# 02-8_Motors.net
KiCad netlist of a schematic drawn in Altium Designer
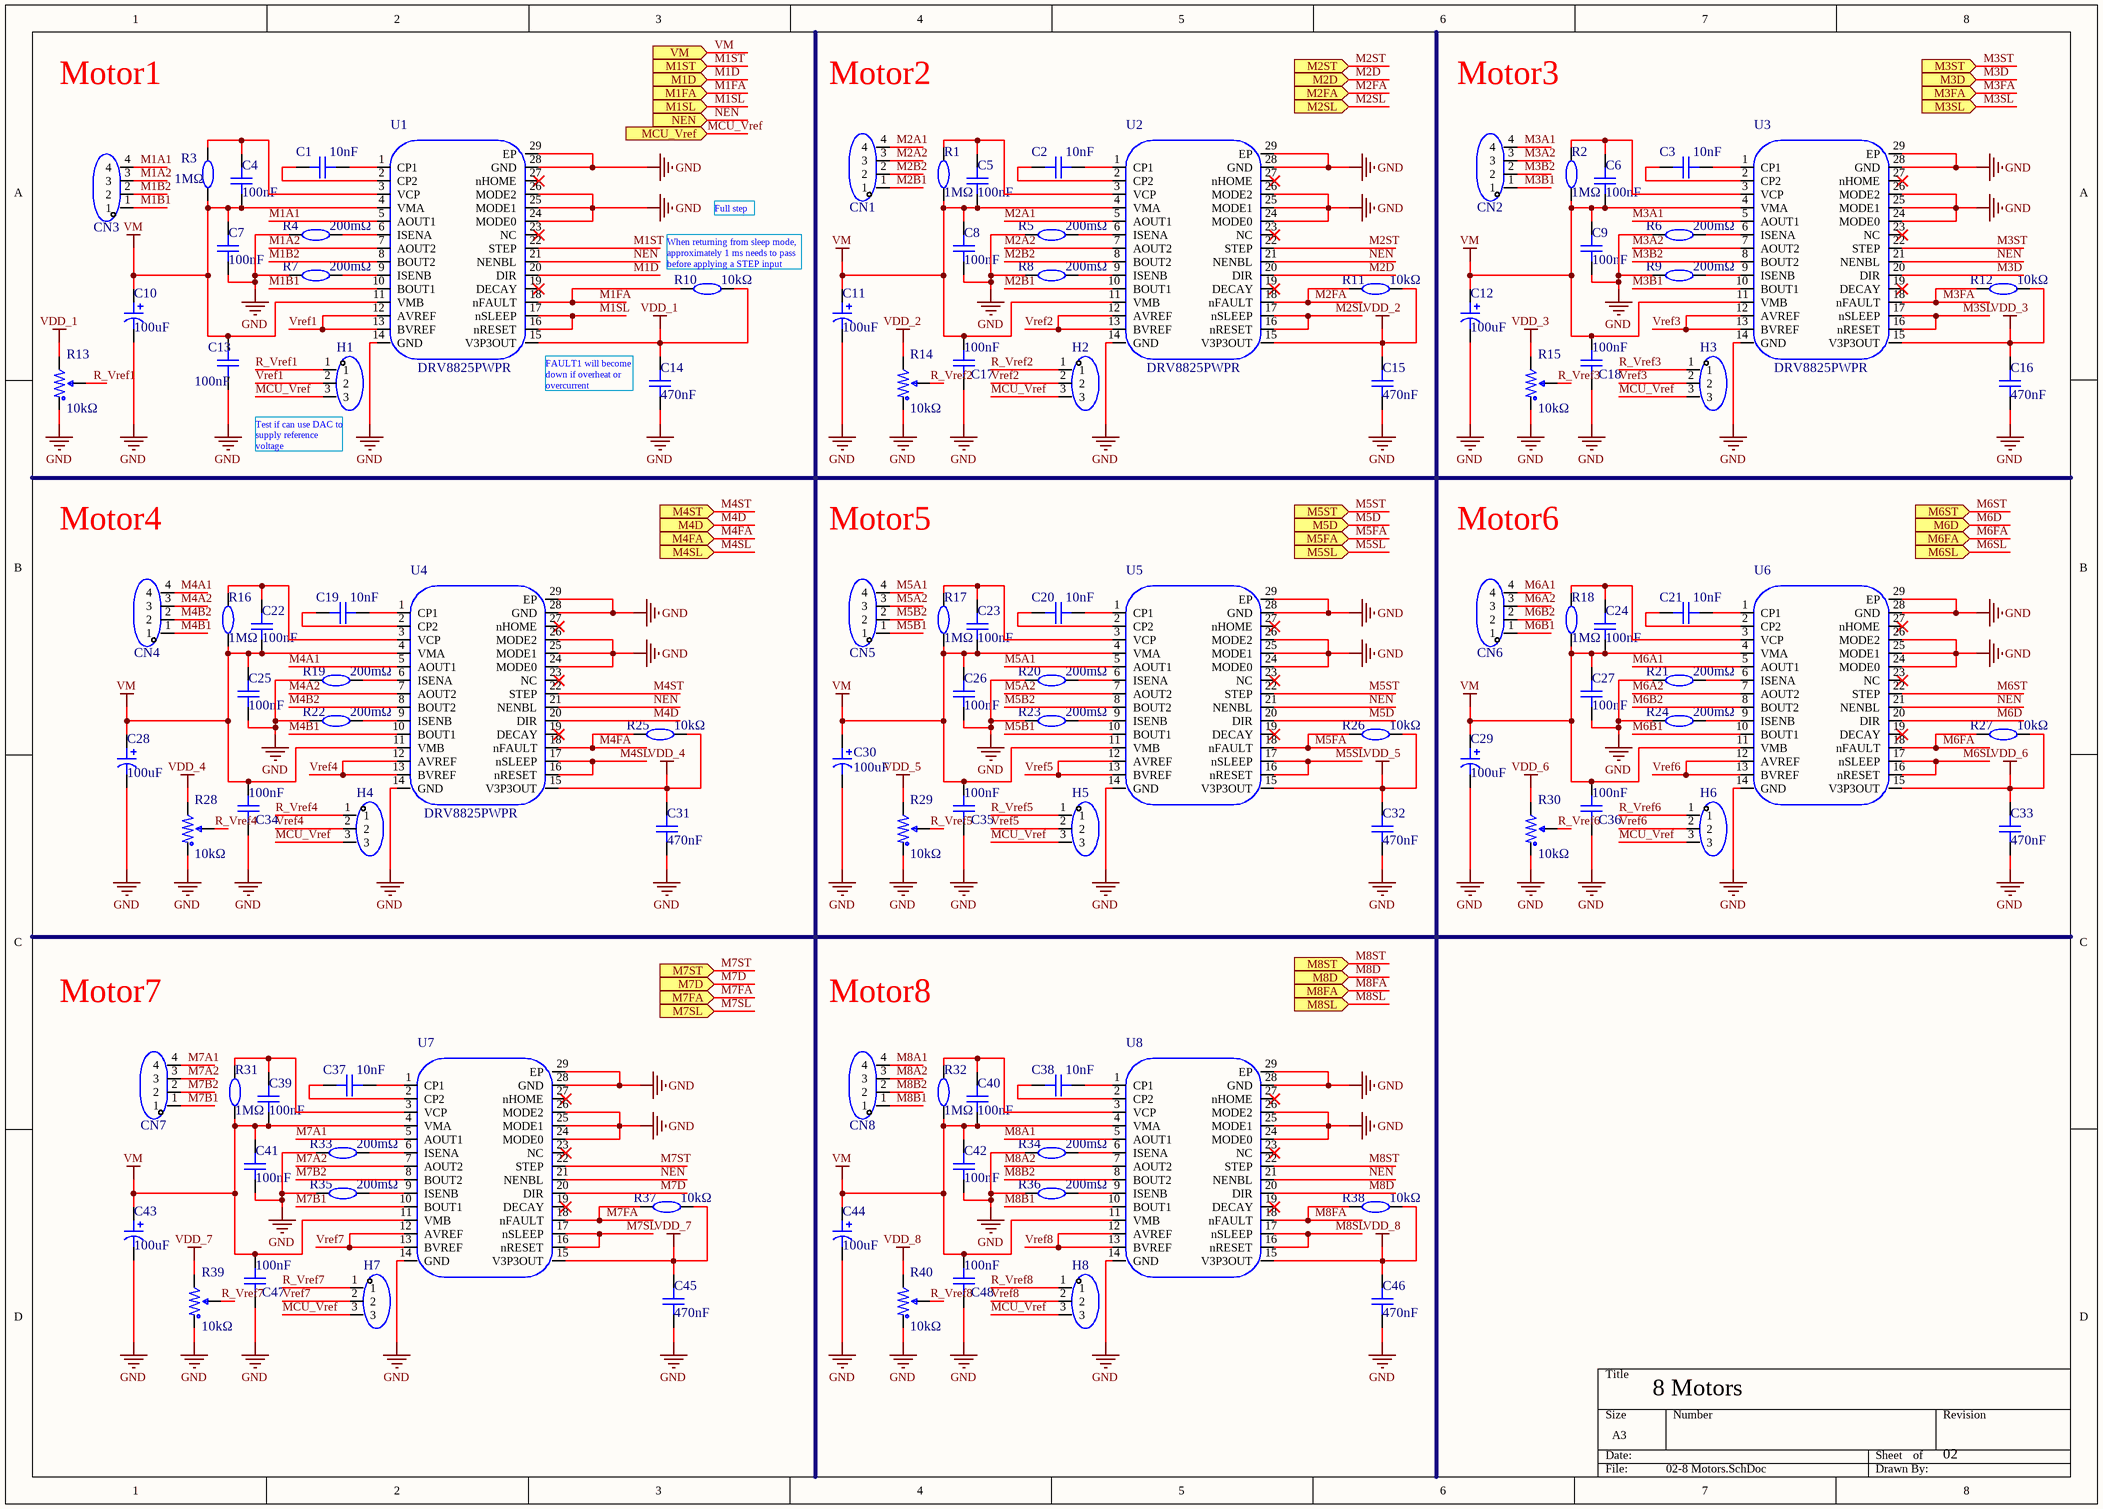
[diagram p0: 02-8 Motors.SchDoc]

(export (version "E")
  (design (tool "Eeschema 10.0.6"))
  (components
    (comp (ref "C1")
      (value "10nF")
      (footprint "C0603")
      (description "0603电容")
      (fields
        (field (name "MANUFACTURER") "SAMSUNG(三星)")
        (field (name "MANUFACTURER PART") "CC0603KRX7R9BB104")
      )
      (libsource (lib "SchLib") (part "C0603_10nF"))
    )
    (comp (ref "C2")
      (value "10nF")
      (footprint "C0603")
      (description "0603电容")
      (fields
        (field (name "MANUFACTURER") "SAMSUNG(三星)")
        (field (name "MANUFACTURER PART") "CC0603KRX7R9BB104")
      )
      (libsource (lib "SchLib") (part "C0603_10nF"))
    )
    (comp (ref "C3")
      (value "10nF")
      (footprint "C0603")
      (description "0603电容")
      (fields
        (field (name "MANUFACTURER") "SAMSUNG(三星)")
        (field (name "MANUFACTURER PART") "CC0603KRX7R9BB104")
      )
      (libsource (lib "SchLib") (part "C0603_10nF"))
    )
    (comp (ref "C4")
      (value "100nF")
      (footprint "C0603")
      (description "0603电容")
      (fields
        (field (name "MANUFACTURER") "SAMSUNG(三星)")
        (field (name "MANUFACTURER PART") "CC0603KRX7R9BB104")
      )
      (libsource (lib "SchLib") (part "C0603_100nF"))
    )
    (comp (ref "C5")
      (value "100nF")
      (footprint "C0603")
      (description "0603电容")
      (fields
        (field (name "MANUFACTURER") "SAMSUNG(三星)")
        (field (name "MANUFACTURER PART") "CC0603KRX7R9BB104")
      )
      (libsource (lib "SchLib") (part "C0603_100nF"))
    )
    (comp (ref "C6")
      (value "100nF")
      (footprint "C0603")
      (description "0603电容")
      (fields
        (field (name "MANUFACTURER") "SAMSUNG(三星)")
        (field (name "MANUFACTURER PART") "CC0603KRX7R9BB104")
      )
      (libsource (lib "SchLib") (part "C0603_100nF"))
    )
    (comp (ref "C7")
      (value "100nF")
      (footprint "C0603")
      (description "0603电容")
      (fields
        (field (name "MANUFACTURER") "SAMSUNG(三星)")
        (field (name "MANUFACTURER PART") "CC0603KRX7R9BB104")
      )
      (libsource (lib "SchLib") (part "C0603_100nF"))
    )
    (comp (ref "C8")
      (value "100nF")
      (footprint "C0603")
      (description "0603电容")
      (fields
        (field (name "MANUFACTURER") "SAMSUNG(三星)")
        (field (name "MANUFACTURER PART") "CC0603KRX7R9BB104")
      )
      (libsource (lib "SchLib") (part "C0603_100nF"))
    )
    (comp (ref "C9")
      (value "100nF")
      (footprint "C0603")
      (description "0603电容")
      (fields
        (field (name "MANUFACTURER") "SAMSUNG(三星)")
        (field (name "MANUFACTURER PART") "CC0603KRX7R9BB104")
      )
      (libsource (lib "SchLib") (part "C0603_100nF"))
    )
    (comp (ref "C10")
      (value "100uF")
      (footprint "SMD6.3_7.7_100uF")
      (description "贴片型铝电解电容 容值 100uF 精度 ±20% 额定电压 35V 纹波电流 87mA@120kHz")
      (fields
        (field (name "MANUFACTURER") "KNSCHA(科尼盛)")
        (field (name "MANUFACTURER PART") "RVT100UF35V67RV0034")
      )
      (libsource (lib "SchLib") (part "SMD6.3_7.7_100uF"))
    )
    (comp (ref "C11")
      (value "100uF")
      (footprint "SMD6.3_7.7_100uF")
      (description "贴片型铝电解电容 容值 100uF 精度 ±20% 额定电压 35V 纹波电流 87mA@120kHz")
      (fields
        (field (name "MANUFACTURER") "KNSCHA(科尼盛)")
        (field (name "MANUFACTURER PART") "RVT100UF35V67RV0034")
      )
      (libsource (lib "SchLib") (part "SMD6.3_7.7_100uF"))
    )
    (comp (ref "C12")
      (value "100uF")
      (footprint "SMD6.3_7.7_100uF")
      (description "贴片型铝电解电容 容值 100uF 精度 ±20% 额定电压 35V 纹波电流 87mA@120kHz")
      (fields
        (field (name "MANUFACTURER") "KNSCHA(科尼盛)")
        (field (name "MANUFACTURER PART") "RVT100UF35V67RV0034")
      )
      (libsource (lib "SchLib") (part "SMD6.3_7.7_100uF"))
    )
    (comp (ref "C13")
      (value "100nF")
      (footprint "C0603")
      (description "0603电容")
      (fields
        (field (name "MANUFACTURER") "SAMSUNG(三星)")
        (field (name "MANUFACTURER PART") "CC0603KRX7R9BB104")
      )
      (libsource (lib "SchLib") (part "C0603_100nF"))
    )
    (comp (ref "C14")
      (value "470nF")
      (footprint "C0603")
      (description "0603电容")
      (fields
        (field (name "MANUFACTURER") "SAMSUNG(三星)")
        (field (name "MANUFACTURER PART") "CC0603KRX7R9BB104")
      )
      (libsource (lib "SchLib") (part "C0603_470nF"))
    )
    (comp (ref "C15")
      (value "470nF")
      (footprint "C0603")
      (description "0603电容")
      (fields
        (field (name "MANUFACTURER") "SAMSUNG(三星)")
        (field (name "MANUFACTURER PART") "CC0603KRX7R9BB104")
      )
      (libsource (lib "SchLib") (part "C0603_470nF"))
    )
    (comp (ref "C16")
      (value "470nF")
      (footprint "C0603")
      (description "0603电容")
      (fields
        (field (name "MANUFACTURER") "SAMSUNG(三星)")
        (field (name "MANUFACTURER PART") "CC0603KRX7R9BB104")
      )
      (libsource (lib "SchLib") (part "C0603_470nF"))
    )
    (comp (ref "C17")
      (value "100nF")
      (footprint "C0603")
      (description "0603电容")
      (fields
        (field (name "MANUFACTURER") "SAMSUNG(三星)")
        (field (name "MANUFACTURER PART") "CC0603KRX7R9BB104")
      )
      (libsource (lib "SchLib") (part "C0603_100nF"))
    )
    (comp (ref "C18")
      (value "100nF")
      (footprint "C0603")
      (description "0603电容")
      (fields
        (field (name "MANUFACTURER") "SAMSUNG(三星)")
        (field (name "MANUFACTURER PART") "CC0603KRX7R9BB104")
      )
      (libsource (lib "SchLib") (part "C0603_100nF"))
    )
    (comp (ref "C19")
      (value "10nF")
      (footprint "C0603")
      (description "0603电容")
      (fields
        (field (name "MANUFACTURER") "SAMSUNG(三星)")
        (field (name "MANUFACTURER PART") "CC0603KRX7R9BB104")
      )
      (libsource (lib "SchLib") (part "C0603_10nF"))
    )
    (comp (ref "C20")
      (value "10nF")
      (footprint "C0603")
      (description "0603电容")
      (fields
        (field (name "MANUFACTURER") "SAMSUNG(三星)")
        (field (name "MANUFACTURER PART") "CC0603KRX7R9BB104")
      )
      (libsource (lib "SchLib") (part "C0603_10nF"))
    )
    (comp (ref "C21")
      (value "10nF")
      (footprint "C0603")
      (description "0603电容")
      (fields
        (field (name "MANUFACTURER") "SAMSUNG(三星)")
        (field (name "MANUFACTURER PART") "CC0603KRX7R9BB104")
      )
      (libsource (lib "SchLib") (part "C0603_10nF"))
    )
    (comp (ref "C22")
      (value "100nF")
      (footprint "C0603")
      (description "0603电容")
      (fields
        (field (name "MANUFACTURER") "SAMSUNG(三星)")
        (field (name "MANUFACTURER PART") "CC0603KRX7R9BB104")
      )
      (libsource (lib "SchLib") (part "C0603_100nF"))
    )
    (comp (ref "C23")
      (value "100nF")
      (footprint "C0603")
      (description "0603电容")
      (fields
        (field (name "MANUFACTURER") "SAMSUNG(三星)")
        (field (name "MANUFACTURER PART") "CC0603KRX7R9BB104")
      )
      (libsource (lib "SchLib") (part "C0603_100nF"))
    )
    (comp (ref "C24")
      (value "100nF")
      (footprint "C0603")
      (description "0603电容")
      (fields
        (field (name "MANUFACTURER") "SAMSUNG(三星)")
        (field (name "MANUFACTURER PART") "CC0603KRX7R9BB104")
      )
      (libsource (lib "SchLib") (part "C0603_100nF"))
    )
    (comp (ref "C25")
      (value "100nF")
      (footprint "C0603")
      (description "0603电容")
      (fields
        (field (name "MANUFACTURER") "SAMSUNG(三星)")
        (field (name "MANUFACTURER PART") "CC0603KRX7R9BB104")
      )
      (libsource (lib "SchLib") (part "C0603_100nF"))
    )
    (comp (ref "C26")
      (value "100nF")
      (footprint "C0603")
      (description "0603电容")
      (fields
        (field (name "MANUFACTURER") "SAMSUNG(三星)")
        (field (name "MANUFACTURER PART") "CC0603KRX7R9BB104")
      )
      (libsource (lib "SchLib") (part "C0603_100nF"))
    )
    (comp (ref "C27")
      (value "100nF")
      (footprint "C0603")
      (description "0603电容")
      (fields
        (field (name "MANUFACTURER") "SAMSUNG(三星)")
        (field (name "MANUFACTURER PART") "CC0603KRX7R9BB104")
      )
      (libsource (lib "SchLib") (part "C0603_100nF"))
    )
    (comp (ref "C28")
      (value "100uF")
      (footprint "SMD6.3_7.7_100uF")
      (description "贴片型铝电解电容 容值 100uF 精度 ±20% 额定电压 35V 纹波电流 87mA@120kHz")
      (fields
        (field (name "MANUFACTURER") "KNSCHA(科尼盛)")
        (field (name "MANUFACTURER PART") "RVT100UF35V67RV0034")
      )
      (libsource (lib "SchLib") (part "SMD6.3_7.7_100uF"))
    )
    (comp (ref "C29")
      (value "100uF")
      (footprint "SMD6.3_7.7_100uF")
      (description "贴片型铝电解电容 容值 100uF 精度 ±20% 额定电压 35V 纹波电流 87mA@120kHz")
      (fields
        (field (name "MANUFACTURER") "KNSCHA(科尼盛)")
        (field (name "MANUFACTURER PART") "RVT100UF35V67RV0034")
      )
      (libsource (lib "SchLib") (part "SMD6.3_7.7_100uF"))
    )
    (comp (ref "C30")
      (value "100uF")
      (footprint "SMD6.3_7.7_100uF")
      (description "贴片型铝电解电容 容值 100uF 精度 ±20% 额定电压 35V 纹波电流 87mA@120kHz")
      (fields
        (field (name "MANUFACTURER") "KNSCHA(科尼盛)")
        (field (name "MANUFACTURER PART") "RVT100UF35V67RV0034")
      )
      (libsource (lib "SchLib") (part "SMD6.3_7.7_100uF"))
    )
    (comp (ref "C31")
      (value "470nF")
      (footprint "C0603")
      (description "0603电容")
      (fields
        (field (name "MANUFACTURER") "SAMSUNG(三星)")
        (field (name "MANUFACTURER PART") "CC0603KRX7R9BB104")
      )
      (libsource (lib "SchLib") (part "C0603_470nF"))
    )
    (comp (ref "C32")
      (value "470nF")
      (footprint "C0603")
      (description "0603电容")
      (fields
        (field (name "MANUFACTURER") "SAMSUNG(三星)")
        (field (name "MANUFACTURER PART") "CC0603KRX7R9BB104")
      )
      (libsource (lib "SchLib") (part "C0603_470nF"))
    )
    (comp (ref "C33")
      (value "470nF")
      (footprint "C0603")
      (description "0603电容")
      (fields
        (field (name "MANUFACTURER") "SAMSUNG(三星)")
        (field (name "MANUFACTURER PART") "CC0603KRX7R9BB104")
      )
      (libsource (lib "SchLib") (part "C0603_470nF"))
    )
    (comp (ref "C34")
      (value "100nF")
      (footprint "C0603")
      (description "0603电容")
      (fields
        (field (name "MANUFACTURER") "SAMSUNG(三星)")
        (field (name "MANUFACTURER PART") "CC0603KRX7R9BB104")
      )
      (libsource (lib "SchLib") (part "C0603_100nF"))
    )
    (comp (ref "C35")
      (value "100nF")
      (footprint "C0603")
      (description "0603电容")
      (fields
        (field (name "MANUFACTURER") "SAMSUNG(三星)")
        (field (name "MANUFACTURER PART") "CC0603KRX7R9BB104")
      )
      (libsource (lib "SchLib") (part "C0603_100nF"))
    )
    (comp (ref "C36")
      (value "100nF")
      (footprint "C0603")
      (description "0603电容")
      (fields
        (field (name "MANUFACTURER") "SAMSUNG(三星)")
        (field (name "MANUFACTURER PART") "CC0603KRX7R9BB104")
      )
      (libsource (lib "SchLib") (part "C0603_100nF"))
    )
    (comp (ref "C37")
      (value "10nF")
      (footprint "C0603")
      (description "0603电容")
      (fields
        (field (name "MANUFACTURER") "SAMSUNG(三星)")
        (field (name "MANUFACTURER PART") "CC0603KRX7R9BB104")
      )
      (libsource (lib "SchLib") (part "C0603_10nF"))
    )
    (comp (ref "C38")
      (value "10nF")
      (footprint "C0603")
      (description "0603电容")
      (fields
        (field (name "MANUFACTURER") "SAMSUNG(三星)")
        (field (name "MANUFACTURER PART") "CC0603KRX7R9BB104")
      )
      (libsource (lib "SchLib") (part "C0603_10nF"))
    )
    (comp (ref "C39")
      (value "100nF")
      (footprint "C0603")
      (description "0603电容")
      (fields
        (field (name "MANUFACTURER") "SAMSUNG(三星)")
        (field (name "MANUFACTURER PART") "CC0603KRX7R9BB104")
      )
      (libsource (lib "SchLib") (part "C0603_100nF"))
    )
    (comp (ref "C40")
      (value "100nF")
      (footprint "C0603")
      (description "0603电容")
      (fields
        (field (name "MANUFACTURER") "SAMSUNG(三星)")
        (field (name "MANUFACTURER PART") "CC0603KRX7R9BB104")
      )
      (libsource (lib "SchLib") (part "C0603_100nF"))
    )
    (comp (ref "C41")
      (value "100nF")
      (footprint "C0603")
      (description "0603电容")
      (fields
        (field (name "MANUFACTURER") "SAMSUNG(三星)")
        (field (name "MANUFACTURER PART") "CC0603KRX7R9BB104")
      )
      (libsource (lib "SchLib") (part "C0603_100nF"))
    )
    (comp (ref "C42")
      (value "100nF")
      (footprint "C0603")
      (description "0603电容")
      (fields
        (field (name "MANUFACTURER") "SAMSUNG(三星)")
        (field (name "MANUFACTURER PART") "CC0603KRX7R9BB104")
      )
      (libsource (lib "SchLib") (part "C0603_100nF"))
    )
    (comp (ref "C43")
      (value "100uF")
      (footprint "SMD6.3_7.7_100uF")
      (description "贴片型铝电解电容 容值 100uF 精度 ±20% 额定电压 35V 纹波电流 87mA@120kHz")
      (fields
        (field (name "MANUFACTURER") "KNSCHA(科尼盛)")
        (field (name "MANUFACTURER PART") "RVT100UF35V67RV0034")
      )
      (libsource (lib "SchLib") (part "SMD6.3_7.7_100uF"))
    )
    (comp (ref "C44")
      (value "100uF")
      (footprint "SMD6.3_7.7_100uF")
      (description "贴片型铝电解电容 容值 100uF 精度 ±20% 额定电压 35V 纹波电流 87mA@120kHz")
      (fields
        (field (name "MANUFACTURER") "KNSCHA(科尼盛)")
        (field (name "MANUFACTURER PART") "RVT100UF35V67RV0034")
      )
      (libsource (lib "SchLib") (part "SMD6.3_7.7_100uF"))
    )
    (comp (ref "C45")
      (value "470nF")
      (footprint "C0603")
      (description "0603电容")
      (fields
        (field (name "MANUFACTURER") "SAMSUNG(三星)")
        (field (name "MANUFACTURER PART") "CC0603KRX7R9BB104")
      )
      (libsource (lib "SchLib") (part "C0603_470nF"))
    )
    (comp (ref "C46")
      (value "470nF")
      (footprint "C0603")
      (description "0603电容")
      (fields
        (field (name "MANUFACTURER") "SAMSUNG(三星)")
        (field (name "MANUFACTURER PART") "CC0603KRX7R9BB104")
      )
      (libsource (lib "SchLib") (part "C0603_470nF"))
    )
    (comp (ref "C47")
      (value "100nF")
      (footprint "C0603")
      (description "0603电容")
      (fields
        (field (name "MANUFACTURER") "SAMSUNG(三星)")
        (field (name "MANUFACTURER PART") "CC0603KRX7R9BB104")
      )
      (libsource (lib "SchLib") (part "C0603_100nF"))
    )
    (comp (ref "C48")
      (value "100nF")
      (footprint "C0603")
      (description "0603电容")
      (fields
        (field (name "MANUFACTURER") "SAMSUNG(三星)")
        (field (name "MANUFACTURER PART") "CC0603KRX7R9BB104")
      )
      (libsource (lib "SchLib") (part "C0603_100nF"))
    )
    (comp (ref "CN1")
      (value "ZX-XH2.54-4PZZ")
      (footprint "ZX-XH2.54-4PZZ")
      (description "直插插针")
      (fields (field (name "MANUFACTURER") "Megastar(兆星)"))
      (libsource (lib "SchLib") (part "ZX-XH2.54-4PZZ"))
    )
    (comp (ref "CN2")
      (value "ZX-XH2.54-4PZZ")
      (footprint "ZX-XH2.54-4PZZ")
      (description "直插插针")
      (fields (field (name "MANUFACTURER") "Megastar(兆星)"))
      (libsource (lib "SchLib") (part "ZX-XH2.54-4PZZ"))
    )
    (comp (ref "CN3")
      (value "ZX-XH2.54-4PZZ")
      (footprint "ZX-XH2.54-4PZZ")
      (description "直插插针")
      (fields (field (name "MANUFACTURER") "Megastar(兆星)"))
      (libsource (lib "SchLib") (part "ZX-XH2.54-4PZZ"))
    )
    (comp (ref "CN4")
      (value "ZX-XH2.54-4PZZ")
      (footprint "ZX-XH2.54-4PZZ")
      (description "直插插针")
      (fields (field (name "MANUFACTURER") "Megastar(兆星)"))
      (libsource (lib "SchLib") (part "ZX-XH2.54-4PZZ"))
    )
    (comp (ref "CN5")
      (value "ZX-XH2.54-4PZZ")
      (footprint "ZX-XH2.54-4PZZ")
      (description "直插插针")
      (fields (field (name "MANUFACTURER") "Megastar(兆星)"))
      (libsource (lib "SchLib") (part "ZX-XH2.54-4PZZ"))
    )
    (comp (ref "CN6")
      (value "ZX-XH2.54-4PZZ")
      (footprint "ZX-XH2.54-4PZZ")
      (description "直插插针")
      (fields (field (name "MANUFACTURER") "Megastar(兆星)"))
      (libsource (lib "SchLib") (part "ZX-XH2.54-4PZZ"))
    )
    (comp (ref "CN7")
      (value "ZX-XH2.54-4PZZ")
      (footprint "ZX-XH2.54-4PZZ")
      (description "直插插针")
      (fields (field (name "MANUFACTURER") "Megastar(兆星)"))
      (libsource (lib "SchLib") (part "ZX-XH2.54-4PZZ"))
    )
    (comp (ref "CN8")
      (value "ZX-XH2.54-4PZZ")
      (footprint "ZX-XH2.54-4PZZ")
      (description "直插插针")
      (fields (field (name "MANUFACTURER") "Megastar(兆星)"))
      (libsource (lib "SchLib") (part "ZX-XH2.54-4PZZ"))
    )
    (comp (ref "H1")
      (value "PZ254V-11-03P")
      (footprint "HC-1.25-3PLT")
      (description "排针3P")
      (fields (field (name "MANUFACTURER") "XFCN(兴飞)"))
      (libsource (lib "SchLib") (part "HC-1.25-3PLT"))
    )
    (comp (ref "H2")
      (value "PZ254V-11-03P")
      (footprint "HC-1.25-3PLT")
      (description "排针3P")
      (fields (field (name "MANUFACTURER") "XFCN(兴飞)"))
      (libsource (lib "SchLib") (part "HC-1.25-3PLT"))
    )
    (comp (ref "H3")
      (value "PZ254V-11-03P")
      (footprint "HC-1.25-3PLT")
      (description "排针3P")
      (fields (field (name "MANUFACTURER") "XFCN(兴飞)"))
      (libsource (lib "SchLib") (part "HC-1.25-3PLT"))
    )
    (comp (ref "H4")
      (value "PZ254V-11-03P")
      (footprint "HC-1.25-3PLT")
      (description "排针3P")
      (fields (field (name "MANUFACTURER") "XFCN(兴飞)"))
      (libsource (lib "SchLib") (part "HC-1.25-3PLT"))
    )
    (comp (ref "H5")
      (value "PZ254V-11-03P")
      (footprint "HC-1.25-3PLT")
      (description "排针3P")
      (fields (field (name "MANUFACTURER") "XFCN(兴飞)"))
      (libsource (lib "SchLib") (part "HC-1.25-3PLT"))
    )
    (comp (ref "H6")
      (value "PZ254V-11-03P")
      (footprint "HC-1.25-3PLT")
      (description "排针3P")
      (fields (field (name "MANUFACTURER") "XFCN(兴飞)"))
      (libsource (lib "SchLib") (part "HC-1.25-3PLT"))
    )
    (comp (ref "H7")
      (value "PZ254V-11-03P")
      (footprint "HC-1.25-3PLT")
      (description "排针3P")
      (fields (field (name "MANUFACTURER") "XFCN(兴飞)"))
      (libsource (lib "SchLib") (part "HC-1.25-3PLT"))
    )
    (comp (ref "H8")
      (value "PZ254V-11-03P")
      (footprint "HC-1.25-3PLT")
      (description "排针3P")
      (fields (field (name "MANUFACTURER") "XFCN(兴飞)"))
      (libsource (lib "SchLib") (part "HC-1.25-3PLT"))
    )
    (comp (ref "R1")
      (value "1MΩ")
      (footprint "R0603")
      (description "0603电阻")
      (fields
        (field (name "MANUFACTURER") "UNI-ROYAL(厚声)")
        (field (name "MANUFACTURER PART") "0603WAF5100T5E")
      )
      (libsource (lib "SchLib") (part "R0603_1MΩ"))
    )
    (comp (ref "R2")
      (value "1MΩ")
      (footprint "R0603")
      (description "0603电阻")
      (fields
        (field (name "MANUFACTURER") "UNI-ROYAL(厚声)")
        (field (name "MANUFACTURER PART") "0603WAF5100T5E")
      )
      (libsource (lib "SchLib") (part "R0603_1MΩ"))
    )
    (comp (ref "R3")
      (value "1MΩ")
      (footprint "R0603")
      (description "0603电阻")
      (fields
        (field (name "MANUFACTURER") "UNI-ROYAL(厚声)")
        (field (name "MANUFACTURER PART") "0603WAF5100T5E")
      )
      (libsource (lib "SchLib") (part "R0603_1MΩ"))
    )
    (comp (ref "R4")
      (value "200mΩ")
      (footprint "R1206_200mΩ")
      (description "1206电阻")
      (fields
        (field (name "MANUFACTURER") "UNI-ROYAL(厚声)")
        (field (name "MANUFACTURER PART") "1206W4F200LT5E")
      )
      (libsource (lib "SchLib") (part "R1206_200mΩ"))
    )
    (comp (ref "R5")
      (value "200mΩ")
      (footprint "R1206_200mΩ")
      (description "1206电阻")
      (fields
        (field (name "MANUFACTURER") "UNI-ROYAL(厚声)")
        (field (name "MANUFACTURER PART") "1206W4F200LT5E")
      )
      (libsource (lib "SchLib") (part "R1206_200mΩ"))
    )
    (comp (ref "R6")
      (value "200mΩ")
      (footprint "R1206_200mΩ")
      (description "1206电阻")
      (fields
        (field (name "MANUFACTURER") "UNI-ROYAL(厚声)")
        (field (name "MANUFACTURER PART") "1206W4F200LT5E")
      )
      (libsource (lib "SchLib") (part "R1206_200mΩ"))
    )
    (comp (ref "R7")
      (value "200mΩ")
      (footprint "R1206_200mΩ")
      (description "1206电阻")
      (fields
        (field (name "MANUFACTURER") "UNI-ROYAL(厚声)")
        (field (name "MANUFACTURER PART") "1206W4F200LT5E")
      )
      (libsource (lib "SchLib") (part "R1206_200mΩ"))
    )
    (comp (ref "R8")
      (value "200mΩ")
      (footprint "R1206_200mΩ")
      (description "1206电阻")
      (fields
        (field (name "MANUFACTURER") "UNI-ROYAL(厚声)")
        (field (name "MANUFACTURER PART") "1206W4F200LT5E")
      )
      (libsource (lib "SchLib") (part "R1206_200mΩ"))
    )
    (comp (ref "R9")
      (value "200mΩ")
      (footprint "R1206_200mΩ")
      (description "1206电阻")
      (fields
        (field (name "MANUFACTURER") "UNI-ROYAL(厚声)")
        (field (name "MANUFACTURER PART") "1206W4F200LT5E")
      )
      (libsource (lib "SchLib") (part "R1206_200mΩ"))
    )
    (comp (ref "R10")
      (value "10kΩ")
      (footprint "R0603_10KΩ")
      (description "0603电阻")
      (fields
        (field (name "MANUFACTURER") "UNI-ROYAL(厚声)")
        (field (name "MANUFACTURER PART") "0603WAF1002T5E")
      )
      (libsource (lib "SchLib") (part "R0603_10KΩ"))
    )
    (comp (ref "R11")
      (value "10kΩ")
      (footprint "R0603_10KΩ")
      (description "0603电阻")
      (fields
        (field (name "MANUFACTURER") "UNI-ROYAL(厚声)")
        (field (name "MANUFACTURER PART") "0603WAF1002T5E")
      )
      (libsource (lib "SchLib") (part "R0603_10KΩ"))
    )
    (comp (ref "R12")
      (value "10kΩ")
      (footprint "R0603_10KΩ")
      (description "0603电阻")
      (fields
        (field (name "MANUFACTURER") "UNI-ROYAL(厚声)")
        (field (name "MANUFACTURER PART") "0603WAF1002T5E")
      )
      (libsource (lib "SchLib") (part "R0603_10KΩ"))
    )
    (comp (ref "R13")
      (value "10kΩ")
      (footprint "R10k_KT")
      (description "可调电阻/电位器   阻值 10kΩ   精度 ±25%   额定电压 -   功率 150mW   温度系数 ±250ppm/℃   圈数 1")
      (fields (field (name "MANUFACTURER") "BOURNS") (field (name "MANUFACTURER PART") "TC33X-2-103E"))
      (libsource (lib "SchLib") (part "R10k_KT"))
    )
    (comp (ref "R14")
      (value "10kΩ")
      (footprint "R10k_KT")
      (description "可调电阻/电位器   阻值 10kΩ   精度 ±25%   额定电压 -   功率 150mW   温度系数 ±250ppm/℃   圈数 1")
      (fields (field (name "MANUFACTURER") "BOURNS") (field (name "MANUFACTURER PART") "TC33X-2-103E"))
      (libsource (lib "SchLib") (part "R10k_KT"))
    )
    (comp (ref "R15")
      (value "10kΩ")
      (footprint "R10k_KT")
      (description "可调电阻/电位器   阻值 10kΩ   精度 ±25%   额定电压 -   功率 150mW   温度系数 ±250ppm/℃   圈数 1")
      (fields (field (name "MANUFACTURER") "BOURNS") (field (name "MANUFACTURER PART") "TC33X-2-103E"))
      (libsource (lib "SchLib") (part "R10k_KT"))
    )
    (comp (ref "R16")
      (value "1MΩ")
      (footprint "R0603")
      (description "0603电阻")
      (fields
        (field (name "MANUFACTURER") "UNI-ROYAL(厚声)")
        (field (name "MANUFACTURER PART") "0603WAF5100T5E")
      )
      (libsource (lib "SchLib") (part "R0603_1MΩ"))
    )
    (comp (ref "R17")
      (value "1MΩ")
      (footprint "R0603")
      (description "0603电阻")
      (fields
        (field (name "MANUFACTURER") "UNI-ROYAL(厚声)")
        (field (name "MANUFACTURER PART") "0603WAF5100T5E")
      )
      (libsource (lib "SchLib") (part "R0603_1MΩ"))
    )
    (comp (ref "R18")
      (value "1MΩ")
      (footprint "R0603")
      (description "0603电阻")
      (fields
        (field (name "MANUFACTURER") "UNI-ROYAL(厚声)")
        (field (name "MANUFACTURER PART") "0603WAF5100T5E")
      )
      (libsource (lib "SchLib") (part "R0603_1MΩ"))
    )
    (comp (ref "R19")
      (value "200mΩ")
      (footprint "R1206_200mΩ")
      (description "1206电阻")
      (fields
        (field (name "MANUFACTURER") "UNI-ROYAL(厚声)")
        (field (name "MANUFACTURER PART") "1206W4F200LT5E")
      )
      (libsource (lib "SchLib") (part "R1206_200mΩ"))
    )
    (comp (ref "R20")
      (value "200mΩ")
      (footprint "R1206_200mΩ")
      (description "1206电阻")
      (fields
        (field (name "MANUFACTURER") "UNI-ROYAL(厚声)")
        (field (name "MANUFACTURER PART") "1206W4F200LT5E")
      )
      (libsource (lib "SchLib") (part "R1206_200mΩ"))
    )
    (comp (ref "R21")
      (value "200mΩ")
      (footprint "R1206_200mΩ")
      (description "1206电阻")
      (fields
        (field (name "MANUFACTURER") "UNI-ROYAL(厚声)")
        (field (name "MANUFACTURER PART") "1206W4F200LT5E")
      )
      (libsource (lib "SchLib") (part "R1206_200mΩ"))
    )
    (comp (ref "R22")
      (value "200mΩ")
      (footprint "R1206_200mΩ")
      (description "1206电阻")
      (fields
        (field (name "MANUFACTURER") "UNI-ROYAL(厚声)")
        (field (name "MANUFACTURER PART") "1206W4F200LT5E")
      )
      (libsource (lib "SchLib") (part "R1206_200mΩ"))
    )
    (comp (ref "R23")
      (value "200mΩ")
      (footprint "R1206_200mΩ")
      (description "1206电阻")
      (fields
        (field (name "MANUFACTURER") "UNI-ROYAL(厚声)")
        (field (name "MANUFACTURER PART") "1206W4F200LT5E")
      )
      (libsource (lib "SchLib") (part "R1206_200mΩ"))
    )
    (comp (ref "R24")
      (value "200mΩ")
      (footprint "R1206_200mΩ")
      (description "1206电阻")
      (fields
        (field (name "MANUFACTURER") "UNI-ROYAL(厚声)")
        (field (name "MANUFACTURER PART") "1206W4F200LT5E")
      )
      (libsource (lib "SchLib") (part "R1206_200mΩ"))
    )
    (comp (ref "R25")
      (value "10kΩ")
      (footprint "R0603_10KΩ")
      (description "0603电阻")
      (fields
        (field (name "MANUFACTURER") "UNI-ROYAL(厚声)")
        (field (name "MANUFACTURER PART") "0603WAF1002T5E")
      )
      (libsource (lib "SchLib") (part "R0603_10KΩ"))
    )
    (comp (ref "R26")
      (value "10kΩ")
      (footprint "R0603_10KΩ")
      (description "0603电阻")
      (fields
        (field (name "MANUFACTURER") "UNI-ROYAL(厚声)")
        (field (name "MANUFACTURER PART") "0603WAF1002T5E")
      )
      (libsource (lib "SchLib") (part "R0603_10KΩ"))
    )
    (comp (ref "R27")
      (value "10kΩ")
      (footprint "R0603_10KΩ")
      (description "0603电阻")
      (fields
        (field (name "MANUFACTURER") "UNI-ROYAL(厚声)")
        (field (name "MANUFACTURER PART") "0603WAF1002T5E")
      )
      (libsource (lib "SchLib") (part "R0603_10KΩ"))
    )
    (comp (ref "R28")
      (value "10kΩ")
      (footprint "R10k_KT")
      (description "可调电阻/电位器   阻值 10kΩ   精度 ±25%   额定电压 -   功率 150mW   温度系数 ±250ppm/℃   圈数 1")
      (fields (field (name "MANUFACTURER") "BOURNS") (field (name "MANUFACTURER PART") "TC33X-2-103E"))
      (libsource (lib "SchLib") (part "R10k_KT"))
    )
    (comp (ref "R29")
      (value "10kΩ")
      (footprint "R10k_KT")
      (description "可调电阻/电位器   阻值 10kΩ   精度 ±25%   额定电压 -   功率 150mW   温度系数 ±250ppm/℃   圈数 1")
      (fields (field (name "MANUFACTURER") "BOURNS") (field (name "MANUFACTURER PART") "TC33X-2-103E"))
      (libsource (lib "SchLib") (part "R10k_KT"))
    )
    (comp (ref "R30")
      (value "10kΩ")
      (footprint "R10k_KT")
      (description "可调电阻/电位器   阻值 10kΩ   精度 ±25%   额定电压 -   功率 150mW   温度系数 ±250ppm/℃   圈数 1")
      (fields (field (name "MANUFACTURER") "BOURNS") (field (name "MANUFACTURER PART") "TC33X-2-103E"))
      (libsource (lib "SchLib") (part "R10k_KT"))
    )
    (comp (ref "R31")
      (value "1MΩ")
      (footprint "R0603")
      (description "0603电阻")
      (fields
        (field (name "MANUFACTURER") "UNI-ROYAL(厚声)")
        (field (name "MANUFACTURER PART") "0603WAF5100T5E")
      )
      (libsource (lib "SchLib") (part "R0603_1MΩ"))
    )
    (comp (ref "R32")
      (value "1MΩ")
      (footprint "R0603")
      (description "0603电阻")
      (fields
        (field (name "MANUFACTURER") "UNI-ROYAL(厚声)")
        (field (name "MANUFACTURER PART") "0603WAF5100T5E")
      )
      (libsource (lib "SchLib") (part "R0603_1MΩ"))
    )
    (comp (ref "R33")
      (value "200mΩ")
      (footprint "R1206_200mΩ")
      (description "1206电阻")
      (fields
        (field (name "MANUFACTURER") "UNI-ROYAL(厚声)")
        (field (name "MANUFACTURER PART") "1206W4F200LT5E")
      )
      (libsource (lib "SchLib") (part "R1206_200mΩ"))
    )
    (comp (ref "R34")
      (value "200mΩ")
      (footprint "R1206_200mΩ")
      (description "1206电阻")
      (fields
        (field (name "MANUFACTURER") "UNI-ROYAL(厚声)")
        (field (name "MANUFACTURER PART") "1206W4F200LT5E")
      )
      (libsource (lib "SchLib") (part "R1206_200mΩ"))
    )
    (comp (ref "R35")
      (value "200mΩ")
      (footprint "R1206_200mΩ")
      (description "1206电阻")
      (fields
        (field (name "MANUFACTURER") "UNI-ROYAL(厚声)")
        (field (name "MANUFACTURER PART") "1206W4F200LT5E")
      )
      (libsource (lib "SchLib") (part "R1206_200mΩ"))
    )
    (comp (ref "R36")
      (value "200mΩ")
      (footprint "R1206_200mΩ")
      (description "1206电阻")
      (fields
        (field (name "MANUFACTURER") "UNI-ROYAL(厚声)")
        (field (name "MANUFACTURER PART") "1206W4F200LT5E")
      )
      (libsource (lib "SchLib") (part "R1206_200mΩ"))
    )
    (comp (ref "R37")
      (value "10kΩ")
      (footprint "R0603_10KΩ")
      (description "0603电阻")
      (fields
        (field (name "MANUFACTURER") "UNI-ROYAL(厚声)")
        (field (name "MANUFACTURER PART") "0603WAF1002T5E")
      )
      (libsource (lib "SchLib") (part "R0603_10KΩ"))
    )
    (comp (ref "R38")
      (value "10kΩ")
      (footprint "R0603_10KΩ")
      (description "0603电阻")
      (fields
        (field (name "MANUFACTURER") "UNI-ROYAL(厚声)")
        (field (name "MANUFACTURER PART") "0603WAF1002T5E")
      )
      (libsource (lib "SchLib") (part "R0603_10KΩ"))
    )
    (comp (ref "R39")
      (value "10kΩ")
      (footprint "R10k_KT")
      (description "可调电阻/电位器   阻值 10kΩ   精度 ±25%   额定电压 -   功率 150mW   温度系数 ±250ppm/℃   圈数 1")
      (fields (field (name "MANUFACTURER") "BOURNS") (field (name "MANUFACTURER PART") "TC33X-2-103E"))
      (libsource (lib "SchLib") (part "R10k_KT"))
    )
    (comp (ref "R40")
      (value "10kΩ")
      (footprint "R10k_KT")
      (description "可调电阻/电位器   阻值 10kΩ   精度 ±25%   额定电压 -   功率 150mW   温度系数 ±250ppm/℃   圈数 1")
      (fields (field (name "MANUFACTURER") "BOURNS") (field (name "MANUFACTURER PART") "TC33X-2-103E"))
      (libsource (lib "SchLib") (part "R10k_KT"))
    )
    (comp (ref "U1")
      (value "DRV8825PWPR")
      (footprint "DRV8825PWPR")
      (description "步进电机驱动芯片")
      (fields (field (name "MANUFACTURER") "TI(德州仪器)"))
      (libsource (lib "SchLib") (part "DRV8825PWPR"))
    )
    (comp (ref "U2")
      (value "DRV8825PWPR")
      (footprint "DRV8825PWPR")
      (description "步进电机驱动芯片")
      (fields (field (name "MANUFACTURER") "TI(德州仪器)"))
      (libsource (lib "SchLib") (part "DRV8825PWPR"))
    )
    (comp (ref "U3")
      (value "DRV8825PWPR")
      (footprint "DRV8825PWPR")
      (description "步进电机驱动芯片")
      (fields (field (name "MANUFACTURER") "TI(德州仪器)"))
      (libsource (lib "SchLib") (part "DRV8825PWPR"))
    )
    (comp (ref "U4")
      (value "DRV8825PWPR")
      (footprint "DRV8825PWPR")
      (description "步进电机驱动芯片")
      (fields (field (name "MANUFACTURER") "TI(德州仪器)"))
      (libsource (lib "SchLib") (part "DRV8825PWPR"))
    )
    (comp (ref "U5")
      (value "DRV8825PWPR")
      (footprint "DRV8825PWPR")
      (description "步进电机驱动芯片")
      (fields (field (name "MANUFACTURER") "TI(德州仪器)"))
      (libsource (lib "SchLib") (part "DRV8825PWPR"))
    )
    (comp (ref "U6")
      (value "DRV8825PWPR")
      (footprint "DRV8825PWPR")
      (description "步进电机驱动芯片")
      (fields (field (name "MANUFACTURER") "TI(德州仪器)"))
      (libsource (lib "SchLib") (part "DRV8825PWPR"))
    )
    (comp (ref "U7")
      (value "DRV8825PWPR")
      (footprint "DRV8825PWPR")
      (description "步进电机驱动芯片")
      (fields (field (name "MANUFACTURER") "TI(德州仪器)"))
      (libsource (lib "SchLib") (part "DRV8825PWPR"))
    )
    (comp (ref "U8")
      (value "DRV8825PWPR")
      (footprint "DRV8825PWPR")
      (description "步进电机驱动芯片")
      (fields (field (name "MANUFACTURER") "TI(德州仪器)"))
      (libsource (lib "SchLib") (part "DRV8825PWPR"))
    )
  )
  (nets
    (net (code "1") (name "/M1A1") (class "Default")
      (node (ref "CN3") (pin "4") (pinfunction "4_4") (pintype "passive"))
      (node (ref "U1") (pin "5") (pinfunction "AOUT1_5") (pintype "passive"))
    )
    (net (code "2") (name "/M1A2") (class "Default")
      (node (ref "CN3") (pin "3") (pinfunction "3_3") (pintype "passive"))
      (node (ref "U1") (pin "7") (pinfunction "AOUT2_7") (pintype "passive"))
    )
    (net (code "3") (name "/M1B1") (class "Default")
      (node (ref "CN3") (pin "1") (pinfunction "1_1") (pintype "passive"))
      (node (ref "U1") (pin "10") (pinfunction "BOUT1_10") (pintype "passive"))
    )
    (net (code "4") (name "/M1B2") (class "Default")
      (node (ref "CN3") (pin "2") (pinfunction "2_2") (pintype "passive"))
      (node (ref "U1") (pin "8") (pinfunction "BOUT2_8") (pintype "passive"))
    )
    (net (code "5") (name "/M1D") (class "Default")
      (node (ref "U1") (pin "20") (pinfunction "DIR_20") (pintype "passive"))
    )
    (net (code "6") (name "/M1FA") (class "Default")
      (node (ref "R10") (pin "1") (pinfunction "1_1") (pintype "passive"))
      (node (ref "U1") (pin "18") (pinfunction "nFAULT_18") (pintype "passive"))
    )
    (net (code "7") (name "/M1SL") (class "Default")
      (node (ref "U1") (pin "16") (pinfunction "nRESET_16") (pintype "passive"))
      (node (ref "U1") (pin "17") (pinfunction "nSLEEP_17") (pintype "passive"))
    )
    (net (code "8") (name "/M1ST") (class "Default")
      (node (ref "U1") (pin "22") (pinfunction "STEP_22") (pintype "passive"))
    )
    (net (code "9") (name "/M2A1") (class "Default")
      (node (ref "CN1") (pin "4") (pinfunction "4_4") (pintype "passive"))
      (node (ref "U2") (pin "5") (pinfunction "AOUT1_5") (pintype "passive"))
    )
    (net (code "10") (name "/M2A2") (class "Default")
      (node (ref "CN1") (pin "3") (pinfunction "3_3") (pintype "passive"))
      (node (ref "U2") (pin "7") (pinfunction "AOUT2_7") (pintype "passive"))
    )
    (net (code "11") (name "/M2B1") (class "Default")
      (node (ref "CN1") (pin "1") (pinfunction "1_1") (pintype "passive"))
      (node (ref "U2") (pin "10") (pinfunction "BOUT1_10") (pintype "passive"))
    )
    (net (code "12") (name "/M2B2") (class "Default")
      (node (ref "CN1") (pin "2") (pinfunction "2_2") (pintype "passive"))
      (node (ref "U2") (pin "8") (pinfunction "BOUT2_8") (pintype "passive"))
    )
    (net (code "13") (name "/M2D") (class "Default")
      (node (ref "U2") (pin "20") (pinfunction "DIR_20") (pintype "passive"))
    )
    (net (code "14") (name "/M2FA") (class "Default")
      (node (ref "R11") (pin "1") (pinfunction "1_1") (pintype "passive"))
      (node (ref "U2") (pin "18") (pinfunction "nFAULT_18") (pintype "passive"))
    )
    (net (code "15") (name "/M2SL") (class "Default")
      (node (ref "U2") (pin "16") (pinfunction "nRESET_16") (pintype "passive"))
      (node (ref "U2") (pin "17") (pinfunction "nSLEEP_17") (pintype "passive"))
    )
    (net (code "16") (name "/M2ST") (class "Default")
      (node (ref "U2") (pin "22") (pinfunction "STEP_22") (pintype "passive"))
    )
    (net (code "17") (name "/M3A1") (class "Default")
      (node (ref "CN2") (pin "4") (pinfunction "4_4") (pintype "passive"))
      (node (ref "U3") (pin "5") (pinfunction "AOUT1_5") (pintype "passive"))
    )
    (net (code "18") (name "/M3A2") (class "Default")
      (node (ref "CN2") (pin "3") (pinfunction "3_3") (pintype "passive"))
      (node (ref "U3") (pin "7") (pinfunction "AOUT2_7") (pintype "passive"))
    )
    (net (code "19") (name "/M3B1") (class "Default")
      (node (ref "CN2") (pin "1") (pinfunction "1_1") (pintype "passive"))
      (node (ref "U3") (pin "10") (pinfunction "BOUT1_10") (pintype "passive"))
    )
    (net (code "20") (name "/M3B2") (class "Default")
      (node (ref "CN2") (pin "2") (pinfunction "2_2") (pintype "passive"))
      (node (ref "U3") (pin "8") (pinfunction "BOUT2_8") (pintype "passive"))
    )
    (net (code "21") (name "/M3D") (class "Default")
      (node (ref "U3") (pin "20") (pinfunction "DIR_20") (pintype "passive"))
    )
    (net (code "22") (name "/M3FA") (class "Default")
      (node (ref "R12") (pin "1") (pinfunction "1_1") (pintype "passive"))
      (node (ref "U3") (pin "18") (pinfunction "nFAULT_18") (pintype "passive"))
    )
    (net (code "23") (name "/M3SL") (class "Default")
      (node (ref "U3") (pin "16") (pinfunction "nRESET_16") (pintype "passive"))
      (node (ref "U3") (pin "17") (pinfunction "nSLEEP_17") (pintype "passive"))
    )
    (net (code "24") (name "/M3ST") (class "Default")
      (node (ref "U3") (pin "22") (pinfunction "STEP_22") (pintype "passive"))
    )
    (net (code "25") (name "/M4A1") (class "Default")
      (node (ref "CN4") (pin "4") (pinfunction "4_4") (pintype "passive"))
      (node (ref "U4") (pin "5") (pinfunction "AOUT1_5") (pintype "passive"))
    )
    (net (code "26") (name "/M4A2") (class "Default")
      (node (ref "CN4") (pin "3") (pinfunction "3_3") (pintype "passive"))
      (node (ref "U4") (pin "7") (pinfunction "AOUT2_7") (pintype "passive"))
    )
    (net (code "27") (name "/M4B1") (class "Default")
      (node (ref "CN4") (pin "1") (pinfunction "1_1") (pintype "passive"))
      (node (ref "U4") (pin "10") (pinfunction "BOUT1_10") (pintype "passive"))
    )
    (net (code "28") (name "/M4B2") (class "Default")
      (node (ref "CN4") (pin "2") (pinfunction "2_2") (pintype "passive"))
      (node (ref "U4") (pin "8") (pinfunction "BOUT2_8") (pintype "passive"))
    )
    (net (code "29") (name "/M4D") (class "Default")
      (node (ref "U4") (pin "20") (pinfunction "DIR_20") (pintype "passive"))
    )
    (net (code "30") (name "/M4FA") (class "Default")
      (node (ref "R25") (pin "1") (pinfunction "1_1") (pintype "passive"))
      (node (ref "U4") (pin "18") (pinfunction "nFAULT_18") (pintype "passive"))
    )
    (net (code "31") (name "/M4SL") (class "Default")
      (node (ref "U4") (pin "16") (pinfunction "nRESET_16") (pintype "passive"))
      (node (ref "U4") (pin "17") (pinfunction "nSLEEP_17") (pintype "passive"))
    )
    (net (code "32") (name "/M4ST") (class "Default")
      (node (ref "U4") (pin "22") (pinfunction "STEP_22") (pintype "passive"))
    )
    (net (code "33") (name "/M5A1") (class "Default")
      (node (ref "CN5") (pin "4") (pinfunction "4_4") (pintype "passive"))
      (node (ref "U5") (pin "5") (pinfunction "AOUT1_5") (pintype "passive"))
    )
    (net (code "34") (name "/M5A2") (class "Default")
      (node (ref "CN5") (pin "3") (pinfunction "3_3") (pintype "passive"))
      (node (ref "U5") (pin "7") (pinfunction "AOUT2_7") (pintype "passive"))
    )
    (net (code "35") (name "/M5B1") (class "Default")
      (node (ref "CN5") (pin "1") (pinfunction "1_1") (pintype "passive"))
      (node (ref "U5") (pin "10") (pinfunction "BOUT1_10") (pintype "passive"))
    )
    (net (code "36") (name "/M5B2") (class "Default")
      (node (ref "CN5") (pin "2") (pinfunction "2_2") (pintype "passive"))
      (node (ref "U5") (pin "8") (pinfunction "BOUT2_8") (pintype "passive"))
    )
    (net (code "37") (name "/M5D") (class "Default")
      (node (ref "U5") (pin "20") (pinfunction "DIR_20") (pintype "passive"))
    )
    (net (code "38") (name "/M5FA") (class "Default")
      (node (ref "R26") (pin "1") (pinfunction "1_1") (pintype "passive"))
      (node (ref "U5") (pin "18") (pinfunction "nFAULT_18") (pintype "passive"))
    )
    (net (code "39") (name "/M5SL") (class "Default")
      (node (ref "U5") (pin "16") (pinfunction "nRESET_16") (pintype "passive"))
      (node (ref "U5") (pin "17") (pinfunction "nSLEEP_17") (pintype "passive"))
    )
    (net (code "40") (name "/M5ST") (class "Default")
      (node (ref "U5") (pin "22") (pinfunction "STEP_22") (pintype "passive"))
    )
    (net (code "41") (name "/M6A1") (class "Default")
      (node (ref "CN6") (pin "4") (pinfunction "4_4") (pintype "passive"))
      (node (ref "U6") (pin "5") (pinfunction "AOUT1_5") (pintype "passive"))
    )
    (net (code "42") (name "/M6A2") (class "Default")
      (node (ref "CN6") (pin "3") (pinfunction "3_3") (pintype "passive"))
      (node (ref "U6") (pin "7") (pinfunction "AOUT2_7") (pintype "passive"))
    )
    (net (code "43") (name "/M6B1") (class "Default")
      (node (ref "CN6") (pin "1") (pinfunction "1_1") (pintype "passive"))
      (node (ref "U6") (pin "10") (pinfunction "BOUT1_10") (pintype "passive"))
    )
    (net (code "44") (name "/M6B2") (class "Default")
      (node (ref "CN6") (pin "2") (pinfunction "2_2") (pintype "passive"))
      (node (ref "U6") (pin "8") (pinfunction "BOUT2_8") (pintype "passive"))
    )
    (net (code "45") (name "/M6D") (class "Default")
      (node (ref "U6") (pin "20") (pinfunction "DIR_20") (pintype "passive"))
    )
    (net (code "46") (name "/M6FA") (class "Default")
      (node (ref "R27") (pin "1") (pinfunction "1_1") (pintype "passive"))
      (node (ref "U6") (pin "18") (pinfunction "nFAULT_18") (pintype "passive"))
    )
    (net (code "47") (name "/M6SL") (class "Default")
      (node (ref "U6") (pin "16") (pinfunction "nRESET_16") (pintype "passive"))
      (node (ref "U6") (pin "17") (pinfunction "nSLEEP_17") (pintype "passive"))
    )
    (net (code "48") (name "/M6ST") (class "Default")
      (node (ref "U6") (pin "22") (pinfunction "STEP_22") (pintype "passive"))
    )
    (net (code "49") (name "/M7A1") (class "Default")
      (node (ref "CN7") (pin "4") (pinfunction "4_4") (pintype "passive"))
      (node (ref "U7") (pin "5") (pinfunction "AOUT1_5") (pintype "passive"))
    )
    (net (code "50") (name "/M7A2") (class "Default")
      (node (ref "CN7") (pin "3") (pinfunction "3_3") (pintype "passive"))
      (node (ref "U7") (pin "7") (pinfunction "AOUT2_7") (pintype "passive"))
    )
    (net (code "51") (name "/M7B1") (class "Default")
      (node (ref "CN7") (pin "1") (pinfunction "1_1") (pintype "passive"))
      (node (ref "U7") (pin "10") (pinfunction "BOUT1_10") (pintype "passive"))
    )
    (net (code "52") (name "/M7B2") (class "Default")
      (node (ref "CN7") (pin "2") (pinfunction "2_2") (pintype "passive"))
      (node (ref "U7") (pin "8") (pinfunction "BOUT2_8") (pintype "passive"))
    )
    (net (code "53") (name "/M7D") (class "Default")
      (node (ref "U7") (pin "20") (pinfunction "DIR_20") (pintype "passive"))
    )
    (net (code "54") (name "/M7FA") (class "Default")
      (node (ref "R37") (pin "1") (pinfunction "1_1") (pintype "passive"))
      (node (ref "U7") (pin "18") (pinfunction "nFAULT_18") (pintype "passive"))
    )
    (net (code "55") (name "/M7SL") (class "Default")
      (node (ref "U7") (pin "16") (pinfunction "nRESET_16") (pintype "passive"))
      (node (ref "U7") (pin "17") (pinfunction "nSLEEP_17") (pintype "passive"))
    )
    (net (code "56") (name "/M7ST") (class "Default")
      (node (ref "U7") (pin "22") (pinfunction "STEP_22") (pintype "passive"))
    )
    (net (code "57") (name "/M8A1") (class "Default")
      (node (ref "CN8") (pin "4") (pinfunction "4_4") (pintype "passive"))
      (node (ref "U8") (pin "5") (pinfunction "AOUT1_5") (pintype "passive"))
    )
    (net (code "58") (name "/M8A2") (class "Default")
      (node (ref "CN8") (pin "3") (pinfunction "3_3") (pintype "passive"))
      (node (ref "U8") (pin "7") (pinfunction "AOUT2_7") (pintype "passive"))
    )
    (net (code "59") (name "/M8B1") (class "Default")
      (node (ref "CN8") (pin "1") (pinfunction "1_1") (pintype "passive"))
      (node (ref "U8") (pin "10") (pinfunction "BOUT1_10") (pintype "passive"))
    )
    (net (code "60") (name "/M8B2") (class "Default")
      (node (ref "CN8") (pin "2") (pinfunction "2_2") (pintype "passive"))
      (node (ref "U8") (pin "8") (pinfunction "BOUT2_8") (pintype "passive"))
    )
    (net (code "61") (name "/M8D") (class "Default")
      (node (ref "U8") (pin "20") (pinfunction "DIR_20") (pintype "passive"))
    )
    (net (code "62") (name "/M8FA") (class "Default")
      (node (ref "R38") (pin "1") (pinfunction "1_1") (pintype "passive"))
      (node (ref "U8") (pin "18") (pinfunction "nFAULT_18") (pintype "passive"))
    )
    (net (code "63") (name "/M8SL") (class "Default")
      (node (ref "U8") (pin "16") (pinfunction "nRESET_16") (pintype "passive"))
      (node (ref "U8") (pin "17") (pinfunction "nSLEEP_17") (pintype "passive"))
    )
    (net (code "64") (name "/M8ST") (class "Default")
      (node (ref "U8") (pin "22") (pinfunction "STEP_22") (pintype "passive"))
    )
    (net (code "65") (name "/MCU_Vref") (class "Default")
      (node (ref "H1") (pin "3") (pinfunction "3_3") (pintype "passive"))
      (node (ref "H2") (pin "3") (pinfunction "3_3") (pintype "passive"))
      (node (ref "H3") (pin "3") (pinfunction "3_3") (pintype "passive"))
      (node (ref "H4") (pin "3") (pinfunction "3_3") (pintype "passive"))
      (node (ref "H5") (pin "3") (pinfunction "3_3") (pintype "passive"))
      (node (ref "H6") (pin "3") (pinfunction "3_3") (pintype "passive"))
      (node (ref "H7") (pin "3") (pinfunction "3_3") (pintype "passive"))
      (node (ref "H8") (pin "3") (pinfunction "3_3") (pintype "passive"))
    )
    (net (code "66") (name "/NEN") (class "Default")
      (node (ref "U1") (pin "21") (pinfunction "NENBL_21") (pintype "passive"))
      (node (ref "U2") (pin "21") (pinfunction "NENBL_21") (pintype "passive"))
      (node (ref "U3") (pin "21") (pinfunction "NENBL_21") (pintype "passive"))
      (node (ref "U4") (pin "21") (pinfunction "NENBL_21") (pintype "passive"))
      (node (ref "U5") (pin "21") (pinfunction "NENBL_21") (pintype "passive"))
      (node (ref "U6") (pin "21") (pinfunction "NENBL_21") (pintype "passive"))
      (node (ref "U7") (pin "21") (pinfunction "NENBL_21") (pintype "passive"))
      (node (ref "U8") (pin "21") (pinfunction "NENBL_21") (pintype "passive"))
    )
    (net (code "67") (name "/R_Vref1") (class "Default")
      (node (ref "H1") (pin "1") (pinfunction "1_1") (pintype "passive"))
      (node (ref "R13") (pin "2") (pinfunction "2_2") (pintype "passive"))
    )
    (net (code "68") (name "/R_Vref2") (class "Default")
      (node (ref "H2") (pin "1") (pinfunction "1_1") (pintype "passive"))
      (node (ref "R14") (pin "2") (pinfunction "2_2") (pintype "passive"))
    )
    (net (code "69") (name "/R_Vref3") (class "Default")
      (node (ref "H3") (pin "1") (pinfunction "1_1") (pintype "passive"))
      (node (ref "R15") (pin "2") (pinfunction "2_2") (pintype "passive"))
    )
    (net (code "70") (name "/R_Vref4") (class "Default")
      (node (ref "H4") (pin "1") (pinfunction "1_1") (pintype "passive"))
      (node (ref "R28") (pin "2") (pinfunction "2_2") (pintype "passive"))
    )
    (net (code "71") (name "/R_Vref5") (class "Default")
      (node (ref "H5") (pin "1") (pinfunction "1_1") (pintype "passive"))
      (node (ref "R29") (pin "2") (pinfunction "2_2") (pintype "passive"))
    )
    (net (code "72") (name "/R_Vref6") (class "Default")
      (node (ref "H6") (pin "1") (pinfunction "1_1") (pintype "passive"))
      (node (ref "R30") (pin "2") (pinfunction "2_2") (pintype "passive"))
    )
    (net (code "73") (name "/R_Vref7") (class "Default")
      (node (ref "H7") (pin "1") (pinfunction "1_1") (pintype "passive"))
      (node (ref "R39") (pin "2") (pinfunction "2_2") (pintype "passive"))
    )
    (net (code "74") (name "/R_Vref8") (class "Default")
      (node (ref "H8") (pin "1") (pinfunction "1_1") (pintype "passive"))
      (node (ref "R40") (pin "2") (pinfunction "2_2") (pintype "passive"))
    )
    (net (code "75") (name "/Vref1") (class "Default")
      (node (ref "H1") (pin "2") (pinfunction "2_2") (pintype "passive"))
      (node (ref "U1") (pin "12") (pinfunction "AVREF_12") (pintype "passive"))
      (node (ref "U1") (pin "13") (pinfunction "BVREF_13") (pintype "passive"))
    )
    (net (code "76") (name "/Vref2") (class "Default")
      (node (ref "H2") (pin "2") (pinfunction "2_2") (pintype "passive"))
      (node (ref "U2") (pin "12") (pinfunction "AVREF_12") (pintype "passive"))
      (node (ref "U2") (pin "13") (pinfunction "BVREF_13") (pintype "passive"))
    )
    (net (code "77") (name "/Vref3") (class "Default")
      (node (ref "H3") (pin "2") (pinfunction "2_2") (pintype "passive"))
      (node (ref "U3") (pin "12") (pinfunction "AVREF_12") (pintype "passive"))
      (node (ref "U3") (pin "13") (pinfunction "BVREF_13") (pintype "passive"))
    )
    (net (code "78") (name "/Vref4") (class "Default")
      (node (ref "H4") (pin "2") (pinfunction "2_2") (pintype "passive"))
      (node (ref "U4") (pin "12") (pinfunction "AVREF_12") (pintype "passive"))
      (node (ref "U4") (pin "13") (pinfunction "BVREF_13") (pintype "passive"))
    )
    (net (code "79") (name "/Vref5") (class "Default")
      (node (ref "H5") (pin "2") (pinfunction "2_2") (pintype "passive"))
      (node (ref "U5") (pin "12") (pinfunction "AVREF_12") (pintype "passive"))
      (node (ref "U5") (pin "13") (pinfunction "BVREF_13") (pintype "passive"))
    )
    (net (code "80") (name "/Vref6") (class "Default")
      (node (ref "H6") (pin "2") (pinfunction "2_2") (pintype "passive"))
      (node (ref "U6") (pin "12") (pinfunction "AVREF_12") (pintype "passive"))
      (node (ref "U6") (pin "13") (pinfunction "BVREF_13") (pintype "passive"))
    )
    (net (code "81") (name "/Vref7") (class "Default")
      (node (ref "H7") (pin "2") (pinfunction "2_2") (pintype "passive"))
      (node (ref "U7") (pin "12") (pinfunction "AVREF_12") (pintype "passive"))
      (node (ref "U7") (pin "13") (pinfunction "BVREF_13") (pintype "passive"))
    )
    (net (code "82") (name "/Vref8") (class "Default")
      (node (ref "H8") (pin "2") (pinfunction "2_2") (pintype "passive"))
      (node (ref "U8") (pin "12") (pinfunction "AVREF_12") (pintype "passive"))
      (node (ref "U8") (pin "13") (pinfunction "BVREF_13") (pintype "passive"))
    )
    (net (code "83") (name "GND") (class "Default")
      (node (ref "C10") (pin "2") (pinfunction "2_2") (pintype "passive"))
      (node (ref "C11") (pin "2") (pinfunction "2_2") (pintype "passive"))
      (node (ref "C12") (pin "2") (pinfunction "2_2") (pintype "passive"))
      (node (ref "C13") (pin "1") (pinfunction "1_1") (pintype "passive"))
      (node (ref "C14") (pin "1") (pinfunction "1_1") (pintype "passive"))
      (node (ref "C15") (pin "1") (pinfunction "1_1") (pintype "passive"))
      (node (ref "C16") (pin "1") (pinfunction "1_1") (pintype "passive"))
      (node (ref "C17") (pin "1") (pinfunction "1_1") (pintype "passive"))
      (node (ref "C18") (pin "1") (pinfunction "1_1") (pintype "passive"))
      (node (ref "C25") (pin "1") (pinfunction "1_1") (pintype "passive"))
      (node (ref "C26") (pin "1") (pinfunction "1_1") (pintype "passive"))
      (node (ref "C27") (pin "1") (pinfunction "1_1") (pintype "passive"))
      (node (ref "C28") (pin "2") (pinfunction "2_2") (pintype "passive"))
      (node (ref "C29") (pin "2") (pinfunction "2_2") (pintype "passive"))
      (node (ref "C30") (pin "2") (pinfunction "2_2") (pintype "passive"))
      (node (ref "C31") (pin "1") (pinfunction "1_1") (pintype "passive"))
      (node (ref "C32") (pin "1") (pinfunction "1_1") (pintype "passive"))
      (node (ref "C33") (pin "1") (pinfunction "1_1") (pintype "passive"))
      (node (ref "C34") (pin "1") (pinfunction "1_1") (pintype "passive"))
      (node (ref "C35") (pin "1") (pinfunction "1_1") (pintype "passive"))
      (node (ref "C36") (pin "1") (pinfunction "1_1") (pintype "passive"))
      (node (ref "C41") (pin "1") (pinfunction "1_1") (pintype "passive"))
      (node (ref "C42") (pin "1") (pinfunction "1_1") (pintype "passive"))
      (node (ref "C43") (pin "2") (pinfunction "2_2") (pintype "passive"))
      (node (ref "C44") (pin "2") (pinfunction "2_2") (pintype "passive"))
      (node (ref "C45") (pin "1") (pinfunction "1_1") (pintype "passive"))
      (node (ref "C46") (pin "1") (pinfunction "1_1") (pintype "passive"))
      (node (ref "C47") (pin "1") (pinfunction "1_1") (pintype "passive"))
      (node (ref "C48") (pin "1") (pinfunction "1_1") (pintype "passive"))
      (node (ref "C7") (pin "1") (pinfunction "1_1") (pintype "passive"))
      (node (ref "C8") (pin "1") (pinfunction "1_1") (pintype "passive"))
      (node (ref "C9") (pin "1") (pinfunction "1_1") (pintype "passive"))
      (node (ref "R13") (pin "1") (pinfunction "1_1") (pintype "passive"))
      (node (ref "R14") (pin "1") (pinfunction "1_1") (pintype "passive"))
      (node (ref "R15") (pin "1") (pinfunction "1_1") (pintype "passive"))
      (node (ref "R19") (pin "1") (pinfunction "1_1") (pintype "passive"))
      (node (ref "R20") (pin "1") (pinfunction "1_1") (pintype "passive"))
      (node (ref "R21") (pin "1") (pinfunction "1_1") (pintype "passive"))
      (node (ref "R22") (pin "1") (pinfunction "1_1") (pintype "passive"))
      (node (ref "R23") (pin "1") (pinfunction "1_1") (pintype "passive"))
      (node (ref "R24") (pin "1") (pinfunction "1_1") (pintype "passive"))
      (node (ref "R28") (pin "1") (pinfunction "1_1") (pintype "passive"))
      (node (ref "R29") (pin "1") (pinfunction "1_1") (pintype "passive"))
      (node (ref "R30") (pin "1") (pinfunction "1_1") (pintype "passive"))
      (node (ref "R33") (pin "1") (pinfunction "1_1") (pintype "passive"))
      (node (ref "R34") (pin "1") (pinfunction "1_1") (pintype "passive"))
      (node (ref "R35") (pin "1") (pinfunction "1_1") (pintype "passive"))
      (node (ref "R36") (pin "1") (pinfunction "1_1") (pintype "passive"))
      (node (ref "R39") (pin "1") (pinfunction "1_1") (pintype "passive"))
      (node (ref "R4") (pin "1") (pinfunction "1_1") (pintype "passive"))
      (node (ref "R40") (pin "1") (pinfunction "1_1") (pintype "passive"))
      (node (ref "R5") (pin "1") (pinfunction "1_1") (pintype "passive"))
      (node (ref "R6") (pin "1") (pinfunction "1_1") (pintype "passive"))
      (node (ref "R7") (pin "1") (pinfunction "1_1") (pintype "passive"))
      (node (ref "R8") (pin "1") (pinfunction "1_1") (pintype "passive"))
      (node (ref "R9") (pin "1") (pinfunction "1_1") (pintype "passive"))
      (node (ref "U1") (pin "14") (pinfunction "GND_14") (pintype "passive"))
      (node (ref "U1") (pin "24") (pinfunction "MODE0_24") (pintype "passive"))
      (node (ref "U1") (pin "25") (pinfunction "MODE1_25") (pintype "passive"))
      (node (ref "U1") (pin "26") (pinfunction "MODE2_26") (pintype "passive"))
      (node (ref "U1") (pin "28") (pinfunction "GND_28") (pintype "passive"))
      (node (ref "U1") (pin "29") (pinfunction "EP_29") (pintype "passive"))
      (node (ref "U2") (pin "14") (pinfunction "GND_14") (pintype "passive"))
      (node (ref "U2") (pin "24") (pinfunction "MODE0_24") (pintype "passive"))
      (node (ref "U2") (pin "25") (pinfunction "MODE1_25") (pintype "passive"))
      (node (ref "U2") (pin "26") (pinfunction "MODE2_26") (pintype "passive"))
      (node (ref "U2") (pin "28") (pinfunction "GND_28") (pintype "passive"))
      (node (ref "U2") (pin "29") (pinfunction "EP_29") (pintype "passive"))
      (node (ref "U3") (pin "14") (pinfunction "GND_14") (pintype "passive"))
      (node (ref "U3") (pin "24") (pinfunction "MODE0_24") (pintype "passive"))
      (node (ref "U3") (pin "25") (pinfunction "MODE1_25") (pintype "passive"))
      (node (ref "U3") (pin "26") (pinfunction "MODE2_26") (pintype "passive"))
      (node (ref "U3") (pin "28") (pinfunction "GND_28") (pintype "passive"))
      (node (ref "U3") (pin "29") (pinfunction "EP_29") (pintype "passive"))
      (node (ref "U4") (pin "14") (pinfunction "GND_14") (pintype "passive"))
      (node (ref "U4") (pin "24") (pinfunction "MODE0_24") (pintype "passive"))
      (node (ref "U4") (pin "25") (pinfunction "MODE1_25") (pintype "passive"))
      (node (ref "U4") (pin "26") (pinfunction "MODE2_26") (pintype "passive"))
      (node (ref "U4") (pin "28") (pinfunction "GND_28") (pintype "passive"))
      (node (ref "U4") (pin "29") (pinfunction "EP_29") (pintype "passive"))
      (node (ref "U5") (pin "14") (pinfunction "GND_14") (pintype "passive"))
      (node (ref "U5") (pin "24") (pinfunction "MODE0_24") (pintype "passive"))
      (node (ref "U5") (pin "25") (pinfunction "MODE1_25") (pintype "passive"))
      (node (ref "U5") (pin "26") (pinfunction "MODE2_26") (pintype "passive"))
      (node (ref "U5") (pin "28") (pinfunction "GND_28") (pintype "passive"))
      (node (ref "U5") (pin "29") (pinfunction "EP_29") (pintype "passive"))
      (node (ref "U6") (pin "14") (pinfunction "GND_14") (pintype "passive"))
      (node (ref "U6") (pin "24") (pinfunction "MODE0_24") (pintype "passive"))
      (node (ref "U6") (pin "25") (pinfunction "MODE1_25") (pintype "passive"))
      (node (ref "U6") (pin "26") (pinfunction "MODE2_26") (pintype "passive"))
      (node (ref "U6") (pin "28") (pinfunction "GND_28") (pintype "passive"))
      (node (ref "U6") (pin "29") (pinfunction "EP_29") (pintype "passive"))
      (node (ref "U7") (pin "14") (pinfunction "GND_14") (pintype "passive"))
      (node (ref "U7") (pin "24") (pinfunction "MODE0_24") (pintype "passive"))
      (node (ref "U7") (pin "25") (pinfunction "MODE1_25") (pintype "passive"))
      (node (ref "U7") (pin "26") (pinfunction "MODE2_26") (pintype "passive"))
      (node (ref "U7") (pin "28") (pinfunction "GND_28") (pintype "passive"))
      (node (ref "U7") (pin "29") (pinfunction "EP_29") (pintype "passive"))
      (node (ref "U8") (pin "14") (pinfunction "GND_14") (pintype "passive"))
      (node (ref "U8") (pin "24") (pinfunction "MODE0_24") (pintype "passive"))
      (node (ref "U8") (pin "25") (pinfunction "MODE1_25") (pintype "passive"))
      (node (ref "U8") (pin "26") (pinfunction "MODE2_26") (pintype "passive"))
      (node (ref "U8") (pin "28") (pinfunction "GND_28") (pintype "passive"))
      (node (ref "U8") (pin "29") (pinfunction "EP_29") (pintype "passive"))
    )
    (net (code "84") (name "Net-(U1-CP1)") (class "Default")
      (node (ref "C1") (pin "2") (pinfunction "2_2") (pintype "passive"))
      (node (ref "U1") (pin "1") (pinfunction "CP1_1") (pintype "passive"))
    )
    (net (code "85") (name "Net-(U1-CP2)") (class "Default")
      (node (ref "C1") (pin "1") (pinfunction "1_1") (pintype "passive"))
      (node (ref "U1") (pin "2") (pinfunction "CP2_2") (pintype "passive"))
    )
    (net (code "86") (name "Net-(U1-ISENA)") (class "Default")
      (node (ref "R4") (pin "2") (pinfunction "2_2") (pintype "passive"))
      (node (ref "U1") (pin "6") (pinfunction "ISENA_6") (pintype "passive"))
    )
    (net (code "87") (name "Net-(U1-ISENB)") (class "Default")
      (node (ref "R7") (pin "2") (pinfunction "2_2") (pintype "passive"))
      (node (ref "U1") (pin "9") (pinfunction "ISENB_9") (pintype "passive"))
    )
    (net (code "88") (name "Net-(U1-VCP)") (class "Default")
      (node (ref "C4") (pin "1") (pinfunction "1_1") (pintype "passive"))
      (node (ref "R3") (pin "2") (pinfunction "2_2") (pintype "passive"))
      (node (ref "U1") (pin "3") (pinfunction "VCP_3") (pintype "passive"))
    )
    (net (code "89") (name "Net-(U2-CP1)") (class "Default")
      (node (ref "C2") (pin "2") (pinfunction "2_2") (pintype "passive"))
      (node (ref "U2") (pin "1") (pinfunction "CP1_1") (pintype "passive"))
    )
    (net (code "90") (name "Net-(U2-CP2)") (class "Default")
      (node (ref "C2") (pin "1") (pinfunction "1_1") (pintype "passive"))
      (node (ref "U2") (pin "2") (pinfunction "CP2_2") (pintype "passive"))
    )
    (net (code "91") (name "Net-(U2-ISENA)") (class "Default")
      (node (ref "R5") (pin "2") (pinfunction "2_2") (pintype "passive"))
      (node (ref "U2") (pin "6") (pinfunction "ISENA_6") (pintype "passive"))
    )
    (net (code "92") (name "Net-(U2-ISENB)") (class "Default")
      (node (ref "R8") (pin "2") (pinfunction "2_2") (pintype "passive"))
      (node (ref "U2") (pin "9") (pinfunction "ISENB_9") (pintype "passive"))
    )
    (net (code "93") (name "Net-(U2-VCP)") (class "Default")
      (node (ref "C5") (pin "1") (pinfunction "1_1") (pintype "passive"))
      (node (ref "R1") (pin "2") (pinfunction "2_2") (pintype "passive"))
      (node (ref "U2") (pin "3") (pinfunction "VCP_3") (pintype "passive"))
    )
    (net (code "94") (name "Net-(U3-CP1)") (class "Default")
      (node (ref "C3") (pin "2") (pinfunction "2_2") (pintype "passive"))
      (node (ref "U3") (pin "1") (pinfunction "CP1_1") (pintype "passive"))
    )
    (net (code "95") (name "Net-(U3-CP2)") (class "Default")
      (node (ref "C3") (pin "1") (pinfunction "1_1") (pintype "passive"))
      (node (ref "U3") (pin "2") (pinfunction "CP2_2") (pintype "passive"))
    )
    (net (code "96") (name "Net-(U3-ISENA)") (class "Default")
      (node (ref "R6") (pin "2") (pinfunction "2_2") (pintype "passive"))
      (node (ref "U3") (pin "6") (pinfunction "ISENA_6") (pintype "passive"))
    )
    (net (code "97") (name "Net-(U3-ISENB)") (class "Default")
      (node (ref "R9") (pin "2") (pinfunction "2_2") (pintype "passive"))
      (node (ref "U3") (pin "9") (pinfunction "ISENB_9") (pintype "passive"))
    )
    (net (code "98") (name "Net-(U3-VCP)") (class "Default")
      (node (ref "C6") (pin "1") (pinfunction "1_1") (pintype "passive"))
      (node (ref "R2") (pin "2") (pinfunction "2_2") (pintype "passive"))
      (node (ref "U3") (pin "3") (pinfunction "VCP_3") (pintype "passive"))
    )
    (net (code "99") (name "Net-(U4-CP1)") (class "Default")
      (node (ref "C19") (pin "2") (pinfunction "2_2") (pintype "passive"))
      (node (ref "U4") (pin "1") (pinfunction "CP1_1") (pintype "passive"))
    )
    (net (code "100") (name "Net-(U4-CP2)") (class "Default")
      (node (ref "C19") (pin "1") (pinfunction "1_1") (pintype "passive"))
      (node (ref "U4") (pin "2") (pinfunction "CP2_2") (pintype "passive"))
    )
    (net (code "101") (name "Net-(U4-ISENA)") (class "Default")
      (node (ref "R19") (pin "2") (pinfunction "2_2") (pintype "passive"))
      (node (ref "U4") (pin "6") (pinfunction "ISENA_6") (pintype "passive"))
    )
    (net (code "102") (name "Net-(U4-ISENB)") (class "Default")
      (node (ref "R22") (pin "2") (pinfunction "2_2") (pintype "passive"))
      (node (ref "U4") (pin "9") (pinfunction "ISENB_9") (pintype "passive"))
    )
    (net (code "103") (name "Net-(U4-VCP)") (class "Default")
      (node (ref "C22") (pin "1") (pinfunction "1_1") (pintype "passive"))
      (node (ref "R16") (pin "2") (pinfunction "2_2") (pintype "passive"))
      (node (ref "U4") (pin "3") (pinfunction "VCP_3") (pintype "passive"))
    )
    (net (code "104") (name "Net-(U5-CP1)") (class "Default")
      (node (ref "C20") (pin "2") (pinfunction "2_2") (pintype "passive"))
      (node (ref "U5") (pin "1") (pinfunction "CP1_1") (pintype "passive"))
    )
    (net (code "105") (name "Net-(U5-CP2)") (class "Default")
      (node (ref "C20") (pin "1") (pinfunction "1_1") (pintype "passive"))
      (node (ref "U5") (pin "2") (pinfunction "CP2_2") (pintype "passive"))
    )
    (net (code "106") (name "Net-(U5-ISENA)") (class "Default")
      (node (ref "R20") (pin "2") (pinfunction "2_2") (pintype "passive"))
      (node (ref "U5") (pin "6") (pinfunction "ISENA_6") (pintype "passive"))
    )
    (net (code "107") (name "Net-(U5-ISENB)") (class "Default")
      (node (ref "R23") (pin "2") (pinfunction "2_2") (pintype "passive"))
      (node (ref "U5") (pin "9") (pinfunction "ISENB_9") (pintype "passive"))
    )
    (net (code "108") (name "Net-(U5-VCP)") (class "Default")
      (node (ref "C23") (pin "1") (pinfunction "1_1") (pintype "passive"))
      (node (ref "R17") (pin "2") (pinfunction "2_2") (pintype "passive"))
      (node (ref "U5") (pin "3") (pinfunction "VCP_3") (pintype "passive"))
    )
    (net (code "109") (name "Net-(U6-CP1)") (class "Default")
      (node (ref "C21") (pin "2") (pinfunction "2_2") (pintype "passive"))
      (node (ref "U6") (pin "1") (pinfunction "CP1_1") (pintype "passive"))
    )
    (net (code "110") (name "Net-(U6-CP2)") (class "Default")
      (node (ref "C21") (pin "1") (pinfunction "1_1") (pintype "passive"))
      (node (ref "U6") (pin "2") (pinfunction "CP2_2") (pintype "passive"))
    )
    (net (code "111") (name "Net-(U6-ISENA)") (class "Default")
      (node (ref "R21") (pin "2") (pinfunction "2_2") (pintype "passive"))
      (node (ref "U6") (pin "6") (pinfunction "ISENA_6") (pintype "passive"))
    )
    (net (code "112") (name "Net-(U6-ISENB)") (class "Default")
      (node (ref "R24") (pin "2") (pinfunction "2_2") (pintype "passive"))
      (node (ref "U6") (pin "9") (pinfunction "ISENB_9") (pintype "passive"))
    )
    (net (code "113") (name "Net-(U6-VCP)") (class "Default")
      (node (ref "C24") (pin "1") (pinfunction "1_1") (pintype "passive"))
      (node (ref "R18") (pin "2") (pinfunction "2_2") (pintype "passive"))
      (node (ref "U6") (pin "3") (pinfunction "VCP_3") (pintype "passive"))
    )
    (net (code "114") (name "Net-(U7-CP1)") (class "Default")
      (node (ref "C37") (pin "2") (pinfunction "2_2") (pintype "passive"))
      (node (ref "U7") (pin "1") (pinfunction "CP1_1") (pintype "passive"))
    )
    (net (code "115") (name "Net-(U7-CP2)") (class "Default")
      (node (ref "C37") (pin "1") (pinfunction "1_1") (pintype "passive"))
      (node (ref "U7") (pin "2") (pinfunction "CP2_2") (pintype "passive"))
    )
    (net (code "116") (name "Net-(U7-ISENA)") (class "Default")
      (node (ref "R33") (pin "2") (pinfunction "2_2") (pintype "passive"))
      (node (ref "U7") (pin "6") (pinfunction "ISENA_6") (pintype "passive"))
    )
    (net (code "117") (name "Net-(U7-ISENB)") (class "Default")
      (node (ref "R35") (pin "2") (pinfunction "2_2") (pintype "passive"))
      (node (ref "U7") (pin "9") (pinfunction "ISENB_9") (pintype "passive"))
    )
    (net (code "118") (name "Net-(U7-VCP)") (class "Default")
      (node (ref "C39") (pin "1") (pinfunction "1_1") (pintype "passive"))
      (node (ref "R31") (pin "2") (pinfunction "2_2") (pintype "passive"))
      (node (ref "U7") (pin "3") (pinfunction "VCP_3") (pintype "passive"))
    )
    (net (code "119") (name "Net-(U8-CP1)") (class "Default")
      (node (ref "C38") (pin "2") (pinfunction "2_2") (pintype "passive"))
      (node (ref "U8") (pin "1") (pinfunction "CP1_1") (pintype "passive"))
    )
    (net (code "120") (name "Net-(U8-CP2)") (class "Default")
      (node (ref "C38") (pin "1") (pinfunction "1_1") (pintype "passive"))
      (node (ref "U8") (pin "2") (pinfunction "CP2_2") (pintype "passive"))
    )
    (net (code "121") (name "Net-(U8-ISENA)") (class "Default")
      (node (ref "R34") (pin "2") (pinfunction "2_2") (pintype "passive"))
      (node (ref "U8") (pin "6") (pinfunction "ISENA_6") (pintype "passive"))
    )
    (net (code "122") (name "Net-(U8-ISENB)") (class "Default")
      (node (ref "R36") (pin "2") (pinfunction "2_2") (pintype "passive"))
      (node (ref "U8") (pin "9") (pinfunction "ISENB_9") (pintype "passive"))
    )
    (net (code "123") (name "Net-(U8-VCP)") (class "Default")
      (node (ref "C40") (pin "1") (pinfunction "1_1") (pintype "passive"))
      (node (ref "R32") (pin "2") (pinfunction "2_2") (pintype "passive"))
      (node (ref "U8") (pin "3") (pinfunction "VCP_3") (pintype "passive"))
    )
    (net (code "124") (name "VDD_1") (class "Default")
      (node (ref "C14") (pin "2") (pinfunction "2_2") (pintype "passive"))
      (node (ref "R10") (pin "2") (pinfunction "2_2") (pintype "passive"))
      (node (ref "R13") (pin "3") (pinfunction "3_3") (pintype "passive"))
      (node (ref "U1") (pin "15") (pinfunction "V3P3OUT_15") (pintype "passive"))
    )
    (net (code "125") (name "VDD_2") (class "Default")
      (node (ref "C15") (pin "2") (pinfunction "2_2") (pintype "passive"))
      (node (ref "R11") (pin "2") (pinfunction "2_2") (pintype "passive"))
      (node (ref "R14") (pin "3") (pinfunction "3_3") (pintype "passive"))
      (node (ref "U2") (pin "15") (pinfunction "V3P3OUT_15") (pintype "passive"))
    )
    (net (code "126") (name "VDD_3") (class "Default")
      (node (ref "C16") (pin "2") (pinfunction "2_2") (pintype "passive"))
      (node (ref "R12") (pin "2") (pinfunction "2_2") (pintype "passive"))
      (node (ref "R15") (pin "3") (pinfunction "3_3") (pintype "passive"))
      (node (ref "U3") (pin "15") (pinfunction "V3P3OUT_15") (pintype "passive"))
    )
    (net (code "127") (name "VDD_4") (class "Default")
      (node (ref "C31") (pin "2") (pinfunction "2_2") (pintype "passive"))
      (node (ref "R25") (pin "2") (pinfunction "2_2") (pintype "passive"))
      (node (ref "R28") (pin "3") (pinfunction "3_3") (pintype "passive"))
      (node (ref "U4") (pin "15") (pinfunction "V3P3OUT_15") (pintype "passive"))
    )
    (net (code "128") (name "VDD_5") (class "Default")
      (node (ref "C32") (pin "2") (pinfunction "2_2") (pintype "passive"))
      (node (ref "R26") (pin "2") (pinfunction "2_2") (pintype "passive"))
      (node (ref "R29") (pin "3") (pinfunction "3_3") (pintype "passive"))
      (node (ref "U5") (pin "15") (pinfunction "V3P3OUT_15") (pintype "passive"))
    )
    (net (code "129") (name "VDD_6") (class "Default")
      (node (ref "C33") (pin "2") (pinfunction "2_2") (pintype "passive"))
      (node (ref "R27") (pin "2") (pinfunction "2_2") (pintype "passive"))
      (node (ref "R30") (pin "3") (pinfunction "3_3") (pintype "passive"))
      (node (ref "U6") (pin "15") (pinfunction "V3P3OUT_15") (pintype "passive"))
    )
    (net (code "130") (name "VDD_7") (class "Default")
      (node (ref "C45") (pin "2") (pinfunction "2_2") (pintype "passive"))
      (node (ref "R37") (pin "2") (pinfunction "2_2") (pintype "passive"))
      (node (ref "R39") (pin "3") (pinfunction "3_3") (pintype "passive"))
      (node (ref "U7") (pin "15") (pinfunction "V3P3OUT_15") (pintype "passive"))
    )
    (net (code "131") (name "VDD_8") (class "Default")
      (node (ref "C46") (pin "2") (pinfunction "2_2") (pintype "passive"))
      (node (ref "R38") (pin "2") (pinfunction "2_2") (pintype "passive"))
      (node (ref "R40") (pin "3") (pinfunction "3_3") (pintype "passive"))
      (node (ref "U8") (pin "15") (pinfunction "V3P3OUT_15") (pintype "passive"))
    )
    (net (code "132") (name "VM") (class "Default")
      (node (ref "C10") (pin "1") (pinfunction "1_1") (pintype "passive"))
      (node (ref "C11") (pin "1") (pinfunction "1_1") (pintype "passive"))
      (node (ref "C12") (pin "1") (pinfunction "1_1") (pintype "passive"))
      (node (ref "C13") (pin "2") (pinfunction "2_2") (pintype "passive"))
      (node (ref "C17") (pin "2") (pinfunction "2_2") (pintype "passive"))
      (node (ref "C18") (pin "2") (pinfunction "2_2") (pintype "passive"))
      (node (ref "C22") (pin "2") (pinfunction "2_2") (pintype "passive"))
      (node (ref "C23") (pin "2") (pinfunction "2_2") (pintype "passive"))
      (node (ref "C24") (pin "2") (pinfunction "2_2") (pintype "passive"))
      (node (ref "C25") (pin "2") (pinfunction "2_2") (pintype "passive"))
      (node (ref "C26") (pin "2") (pinfunction "2_2") (pintype "passive"))
      (node (ref "C27") (pin "2") (pinfunction "2_2") (pintype "passive"))
      (node (ref "C28") (pin "1") (pinfunction "1_1") (pintype "passive"))
      (node (ref "C29") (pin "1") (pinfunction "1_1") (pintype "passive"))
      (node (ref "C30") (pin "1") (pinfunction "1_1") (pintype "passive"))
      (node (ref "C34") (pin "2") (pinfunction "2_2") (pintype "passive"))
      (node (ref "C35") (pin "2") (pinfunction "2_2") (pintype "passive"))
      (node (ref "C36") (pin "2") (pinfunction "2_2") (pintype "passive"))
      (node (ref "C39") (pin "2") (pinfunction "2_2") (pintype "passive"))
      (node (ref "C4") (pin "2") (pinfunction "2_2") (pintype "passive"))
      (node (ref "C40") (pin "2") (pinfunction "2_2") (pintype "passive"))
      (node (ref "C41") (pin "2") (pinfunction "2_2") (pintype "passive"))
      (node (ref "C42") (pin "2") (pinfunction "2_2") (pintype "passive"))
      (node (ref "C43") (pin "1") (pinfunction "1_1") (pintype "passive"))
      (node (ref "C44") (pin "1") (pinfunction "1_1") (pintype "passive"))
      (node (ref "C47") (pin "2") (pinfunction "2_2") (pintype "passive"))
      (node (ref "C48") (pin "2") (pinfunction "2_2") (pintype "passive"))
      (node (ref "C5") (pin "2") (pinfunction "2_2") (pintype "passive"))
      (node (ref "C6") (pin "2") (pinfunction "2_2") (pintype "passive"))
      (node (ref "C7") (pin "2") (pinfunction "2_2") (pintype "passive"))
      (node (ref "C8") (pin "2") (pinfunction "2_2") (pintype "passive"))
      (node (ref "C9") (pin "2") (pinfunction "2_2") (pintype "passive"))
      (node (ref "R1") (pin "1") (pinfunction "1_1") (pintype "passive"))
      (node (ref "R16") (pin "1") (pinfunction "1_1") (pintype "passive"))
      (node (ref "R17") (pin "1") (pinfunction "1_1") (pintype "passive"))
      (node (ref "R18") (pin "1") (pinfunction "1_1") (pintype "passive"))
      (node (ref "R2") (pin "1") (pinfunction "1_1") (pintype "passive"))
      (node (ref "R3") (pin "1") (pinfunction "1_1") (pintype "passive"))
      (node (ref "R31") (pin "1") (pinfunction "1_1") (pintype "passive"))
      (node (ref "R32") (pin "1") (pinfunction "1_1") (pintype "passive"))
      (node (ref "U1") (pin "11") (pinfunction "VMB_11") (pintype "passive"))
      (node (ref "U1") (pin "4") (pinfunction "VMA_4") (pintype "passive"))
      (node (ref "U2") (pin "11") (pinfunction "VMB_11") (pintype "passive"))
      (node (ref "U2") (pin "4") (pinfunction "VMA_4") (pintype "passive"))
      (node (ref "U3") (pin "11") (pinfunction "VMB_11") (pintype "passive"))
      (node (ref "U3") (pin "4") (pinfunction "VMA_4") (pintype "passive"))
      (node (ref "U4") (pin "11") (pinfunction "VMB_11") (pintype "passive"))
      (node (ref "U4") (pin "4") (pinfunction "VMA_4") (pintype "passive"))
      (node (ref "U5") (pin "11") (pinfunction "VMB_11") (pintype "passive"))
      (node (ref "U5") (pin "4") (pinfunction "VMA_4") (pintype "passive"))
      (node (ref "U6") (pin "11") (pinfunction "VMB_11") (pintype "passive"))
      (node (ref "U6") (pin "4") (pinfunction "VMA_4") (pintype "passive"))
      (node (ref "U7") (pin "11") (pinfunction "VMB_11") (pintype "passive"))
      (node (ref "U7") (pin "4") (pinfunction "VMA_4") (pintype "passive"))
      (node (ref "U8") (pin "11") (pinfunction "VMB_11") (pintype "passive"))
      (node (ref "U8") (pin "4") (pinfunction "VMA_4") (pintype "passive"))
    )
    (net (code "133") (name "unconnected-(U1-DECAY-Pad19)") (class "Default")
      (node (ref "U1") (pin "19") (pinfunction "DECAY_19") (pintype "passive+no_connect"))
    )
    (net (code "134") (name "unconnected-(U1-NC-Pad23)") (class "Default")
      (node (ref "U1") (pin "23") (pinfunction "NC_23") (pintype "passive+no_connect"))
    )
    (net (code "135") (name "unconnected-(U1-nHOME-Pad27)") (class "Default")
      (node (ref "U1") (pin "27") (pinfunction "nHOME_27") (pintype "passive+no_connect"))
    )
    (net (code "136") (name "unconnected-(U2-DECAY-Pad19)") (class "Default")
      (node (ref "U2") (pin "19") (pinfunction "DECAY_19") (pintype "passive+no_connect"))
    )
    (net (code "137") (name "unconnected-(U2-NC-Pad23)") (class "Default")
      (node (ref "U2") (pin "23") (pinfunction "NC_23") (pintype "passive+no_connect"))
    )
    (net (code "138") (name "unconnected-(U2-nHOME-Pad27)") (class "Default")
      (node (ref "U2") (pin "27") (pinfunction "nHOME_27") (pintype "passive+no_connect"))
    )
    (net (code "139") (name "unconnected-(U3-DECAY-Pad19)") (class "Default")
      (node (ref "U3") (pin "19") (pinfunction "DECAY_19") (pintype "passive+no_connect"))
    )
    (net (code "140") (name "unconnected-(U3-NC-Pad23)") (class "Default")
      (node (ref "U3") (pin "23") (pinfunction "NC_23") (pintype "passive+no_connect"))
    )
    (net (code "141") (name "unconnected-(U3-nHOME-Pad27)") (class "Default")
      (node (ref "U3") (pin "27") (pinfunction "nHOME_27") (pintype "passive+no_connect"))
    )
    (net (code "142") (name "unconnected-(U4-DECAY-Pad19)") (class "Default")
      (node (ref "U4") (pin "19") (pinfunction "DECAY_19") (pintype "passive+no_connect"))
    )
    (net (code "143") (name "unconnected-(U4-NC-Pad23)") (class "Default")
      (node (ref "U4") (pin "23") (pinfunction "NC_23") (pintype "passive+no_connect"))
    )
    (net (code "144") (name "unconnected-(U4-nHOME-Pad27)") (class "Default")
      (node (ref "U4") (pin "27") (pinfunction "nHOME_27") (pintype "passive+no_connect"))
    )
    (net (code "145") (name "unconnected-(U5-DECAY-Pad19)") (class "Default")
      (node (ref "U5") (pin "19") (pinfunction "DECAY_19") (pintype "passive+no_connect"))
    )
    (net (code "146") (name "unconnected-(U5-NC-Pad23)") (class "Default")
      (node (ref "U5") (pin "23") (pinfunction "NC_23") (pintype "passive+no_connect"))
    )
    (net (code "147") (name "unconnected-(U5-nHOME-Pad27)") (class "Default")
      (node (ref "U5") (pin "27") (pinfunction "nHOME_27") (pintype "passive+no_connect"))
    )
    (net (code "148") (name "unconnected-(U6-DECAY-Pad19)") (class "Default")
      (node (ref "U6") (pin "19") (pinfunction "DECAY_19") (pintype "passive+no_connect"))
    )
    (net (code "149") (name "unconnected-(U6-NC-Pad23)") (class "Default")
      (node (ref "U6") (pin "23") (pinfunction "NC_23") (pintype "passive+no_connect"))
    )
    (net (code "150") (name "unconnected-(U6-nHOME-Pad27)") (class "Default")
      (node (ref "U6") (pin "27") (pinfunction "nHOME_27") (pintype "passive+no_connect"))
    )
    (net (code "151") (name "unconnected-(U7-DECAY-Pad19)") (class "Default")
      (node (ref "U7") (pin "19") (pinfunction "DECAY_19") (pintype "passive+no_connect"))
    )
    (net (code "152") (name "unconnected-(U7-NC-Pad23)") (class "Default")
      (node (ref "U7") (pin "23") (pinfunction "NC_23") (pintype "passive+no_connect"))
    )
    (net (code "153") (name "unconnected-(U7-nHOME-Pad27)") (class "Default")
      (node (ref "U7") (pin "27") (pinfunction "nHOME_27") (pintype "passive+no_connect"))
    )
    (net (code "154") (name "unconnected-(U8-DECAY-Pad19)") (class "Default")
      (node (ref "U8") (pin "19") (pinfunction "DECAY_19") (pintype "passive+no_connect"))
    )
    (net (code "155") (name "unconnected-(U8-NC-Pad23)") (class "Default")
      (node (ref "U8") (pin "23") (pinfunction "NC_23") (pintype "passive+no_connect"))
    )
    (net (code "156") (name "unconnected-(U8-nHOME-Pad27)") (class "Default")
      (node (ref "U8") (pin "27") (pinfunction "nHOME_27") (pintype "passive+no_connect"))
    )
  )
)
